# Modular_RFPA_RevA.net
KiCad netlist of a schematic drawn in EAGLE
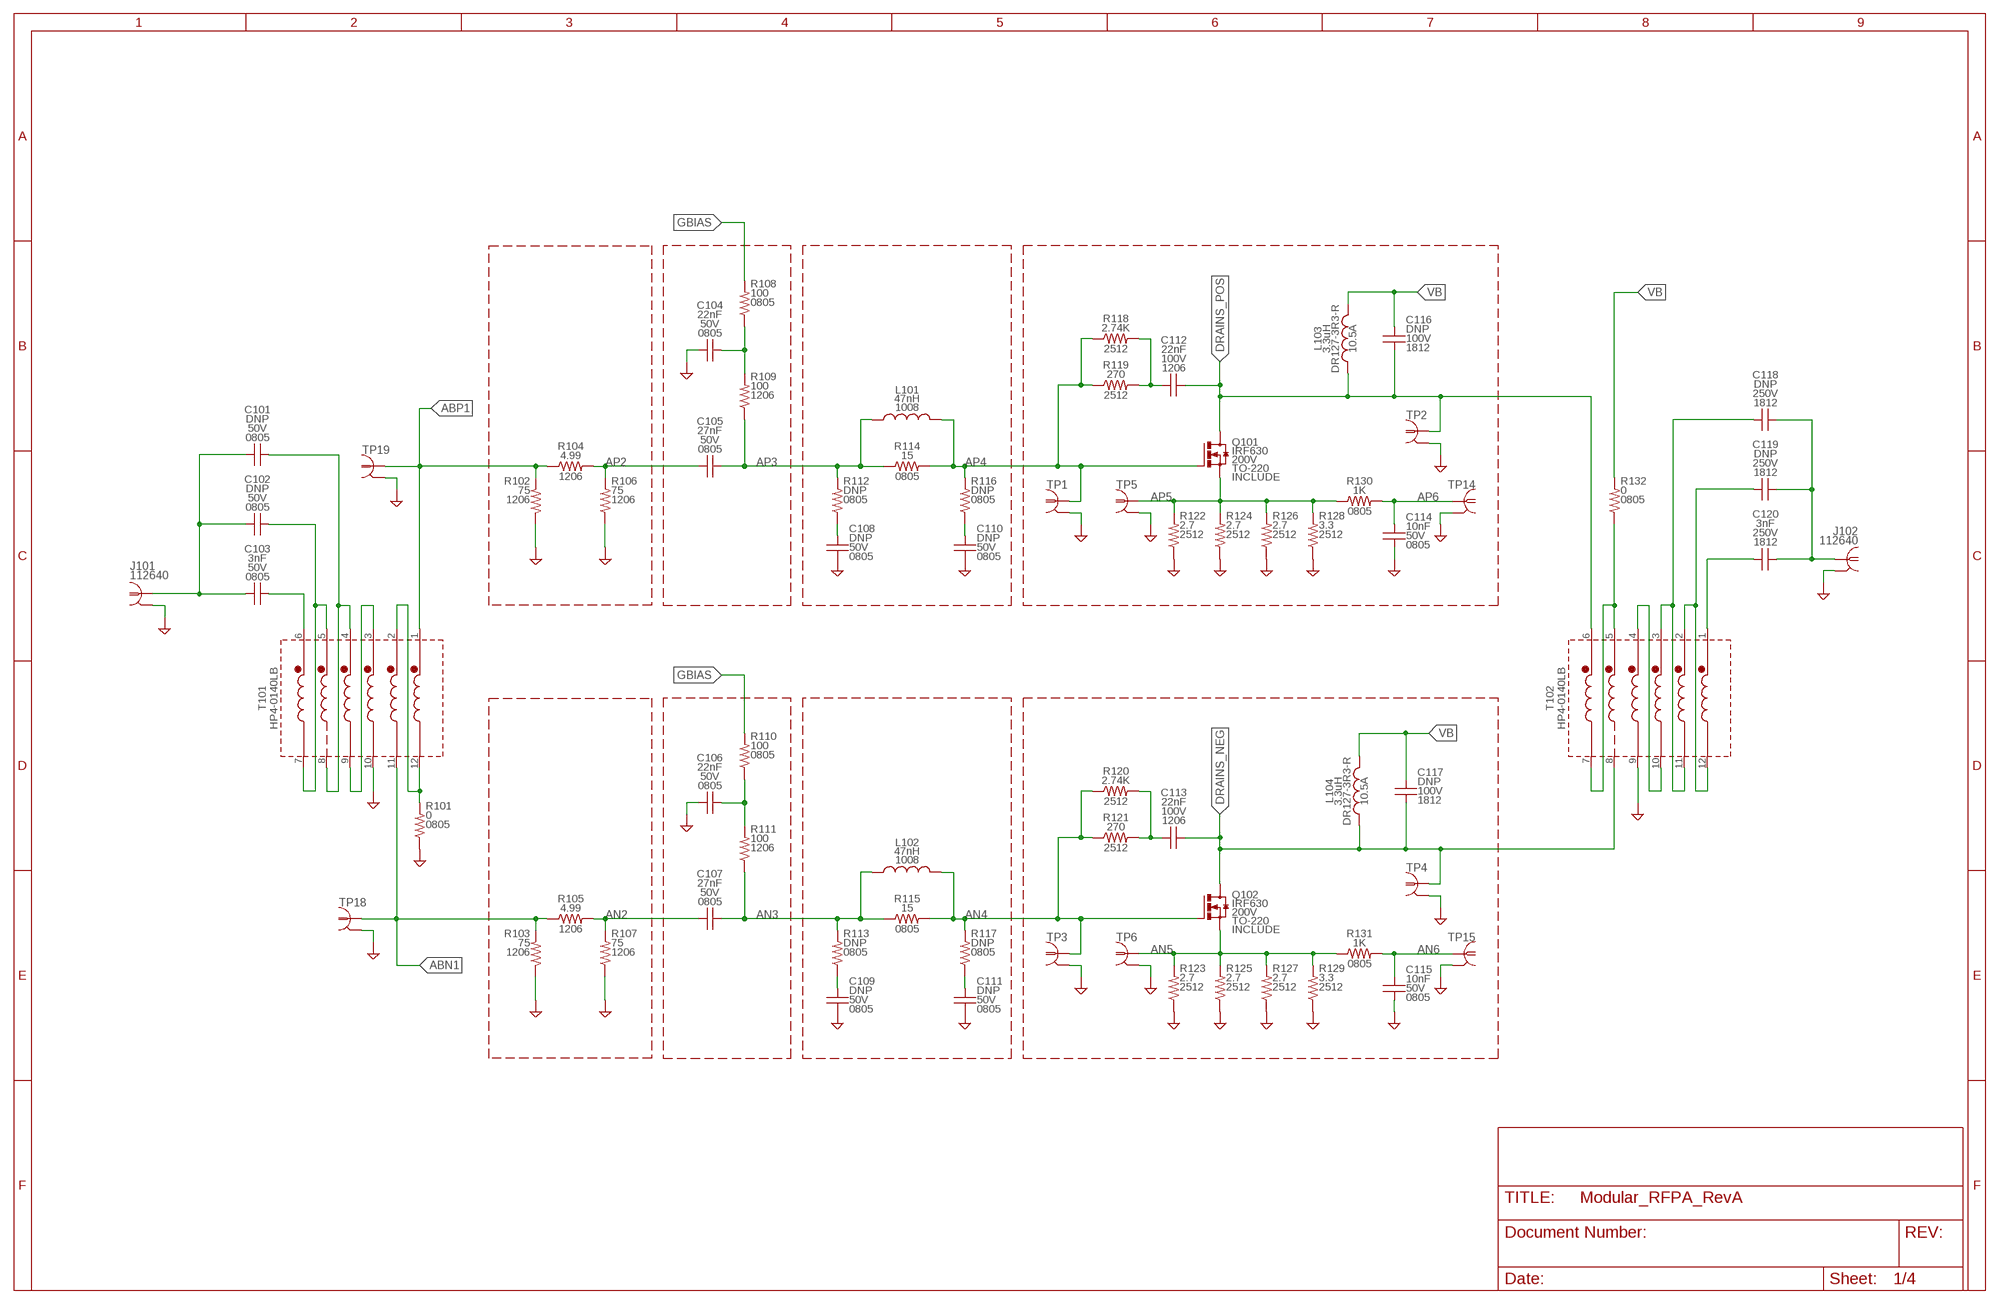
[diagram p0: schematic, sheet 1]
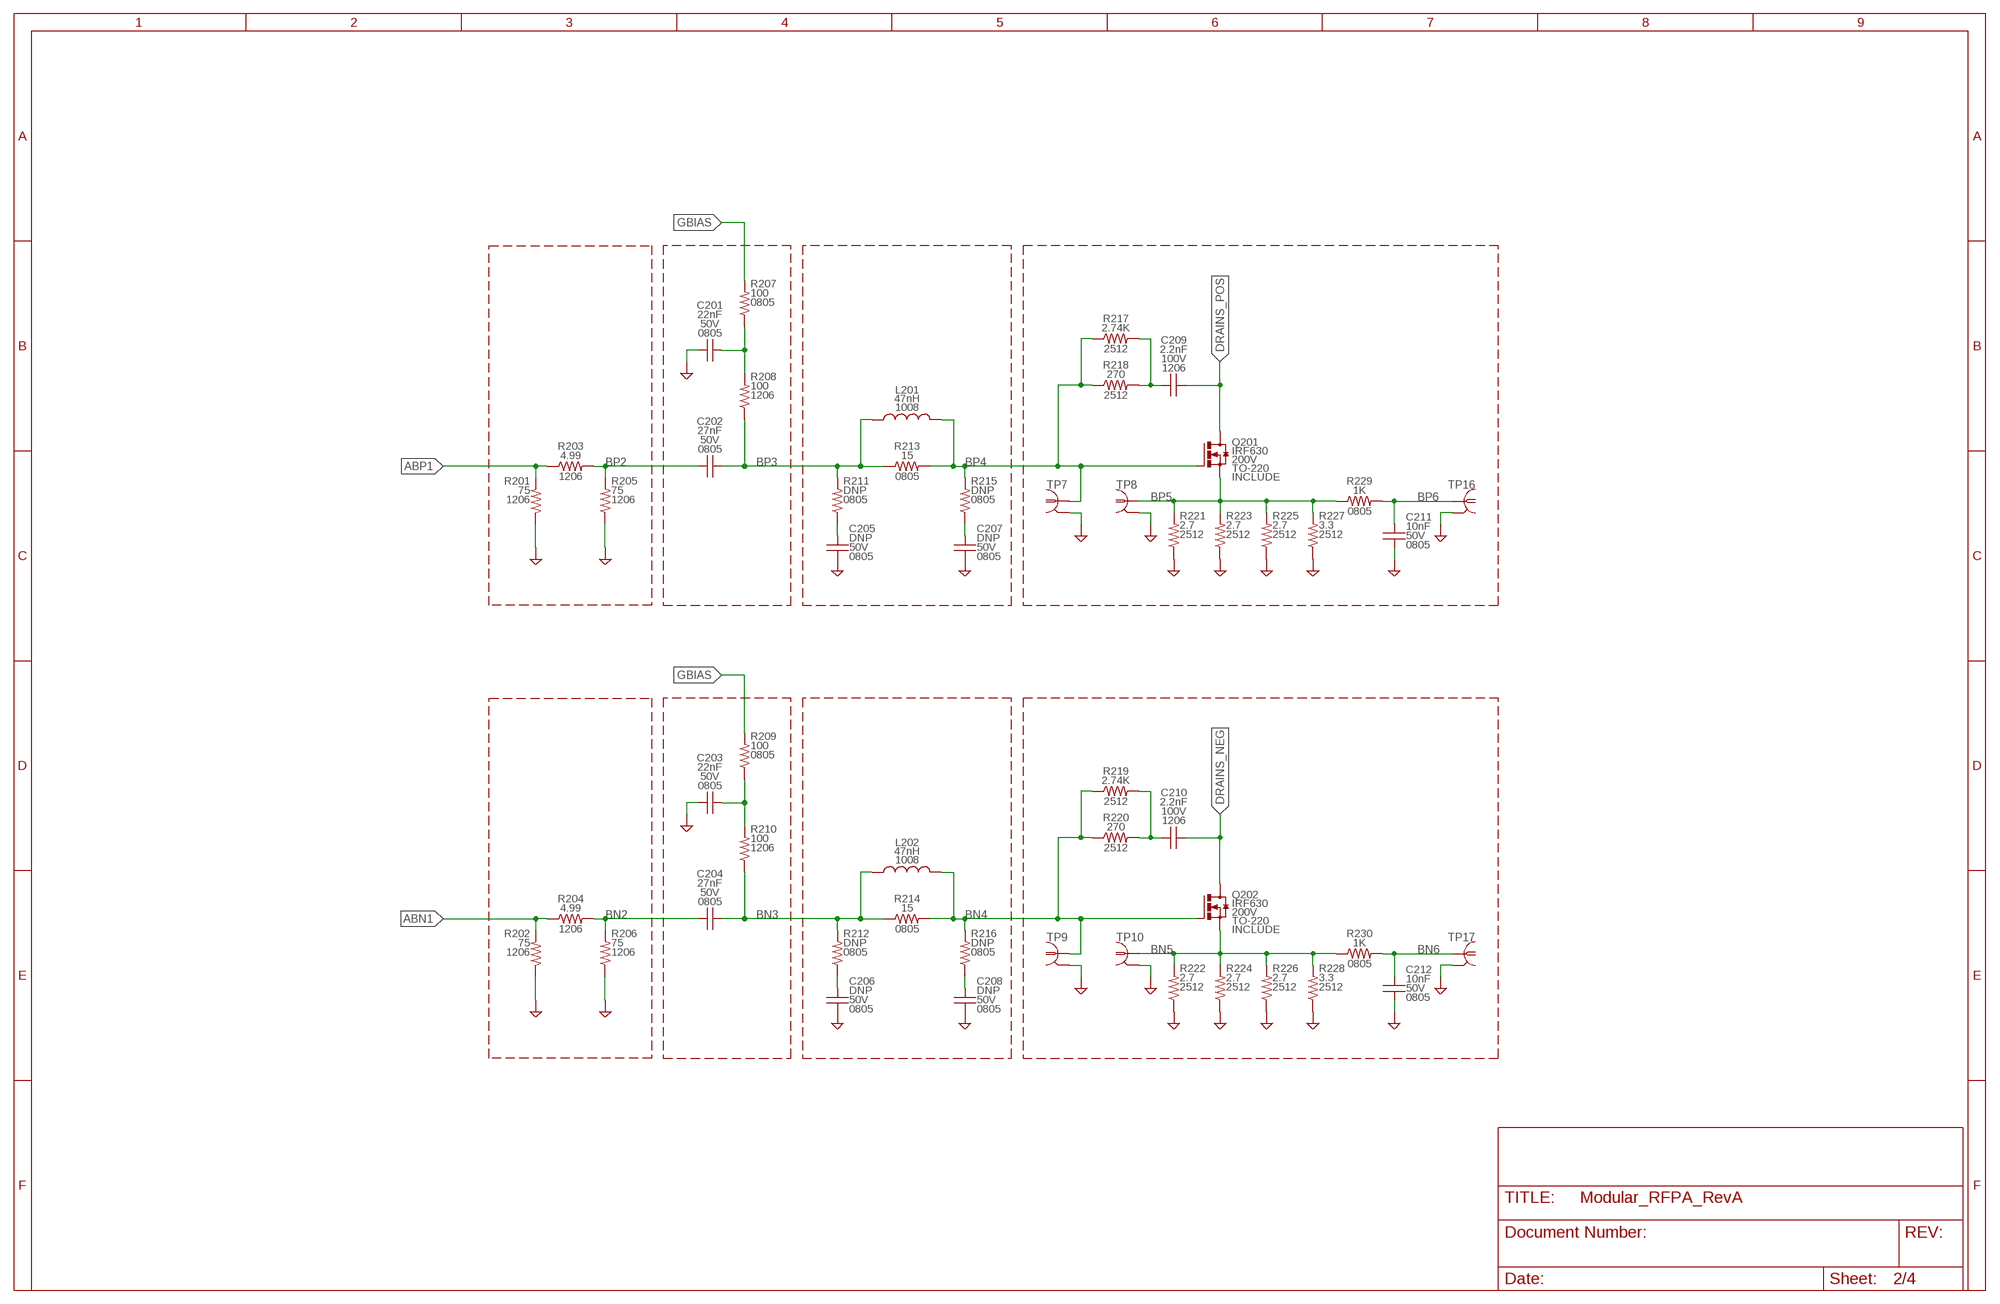
[diagram p1: schematic, sheet 2]
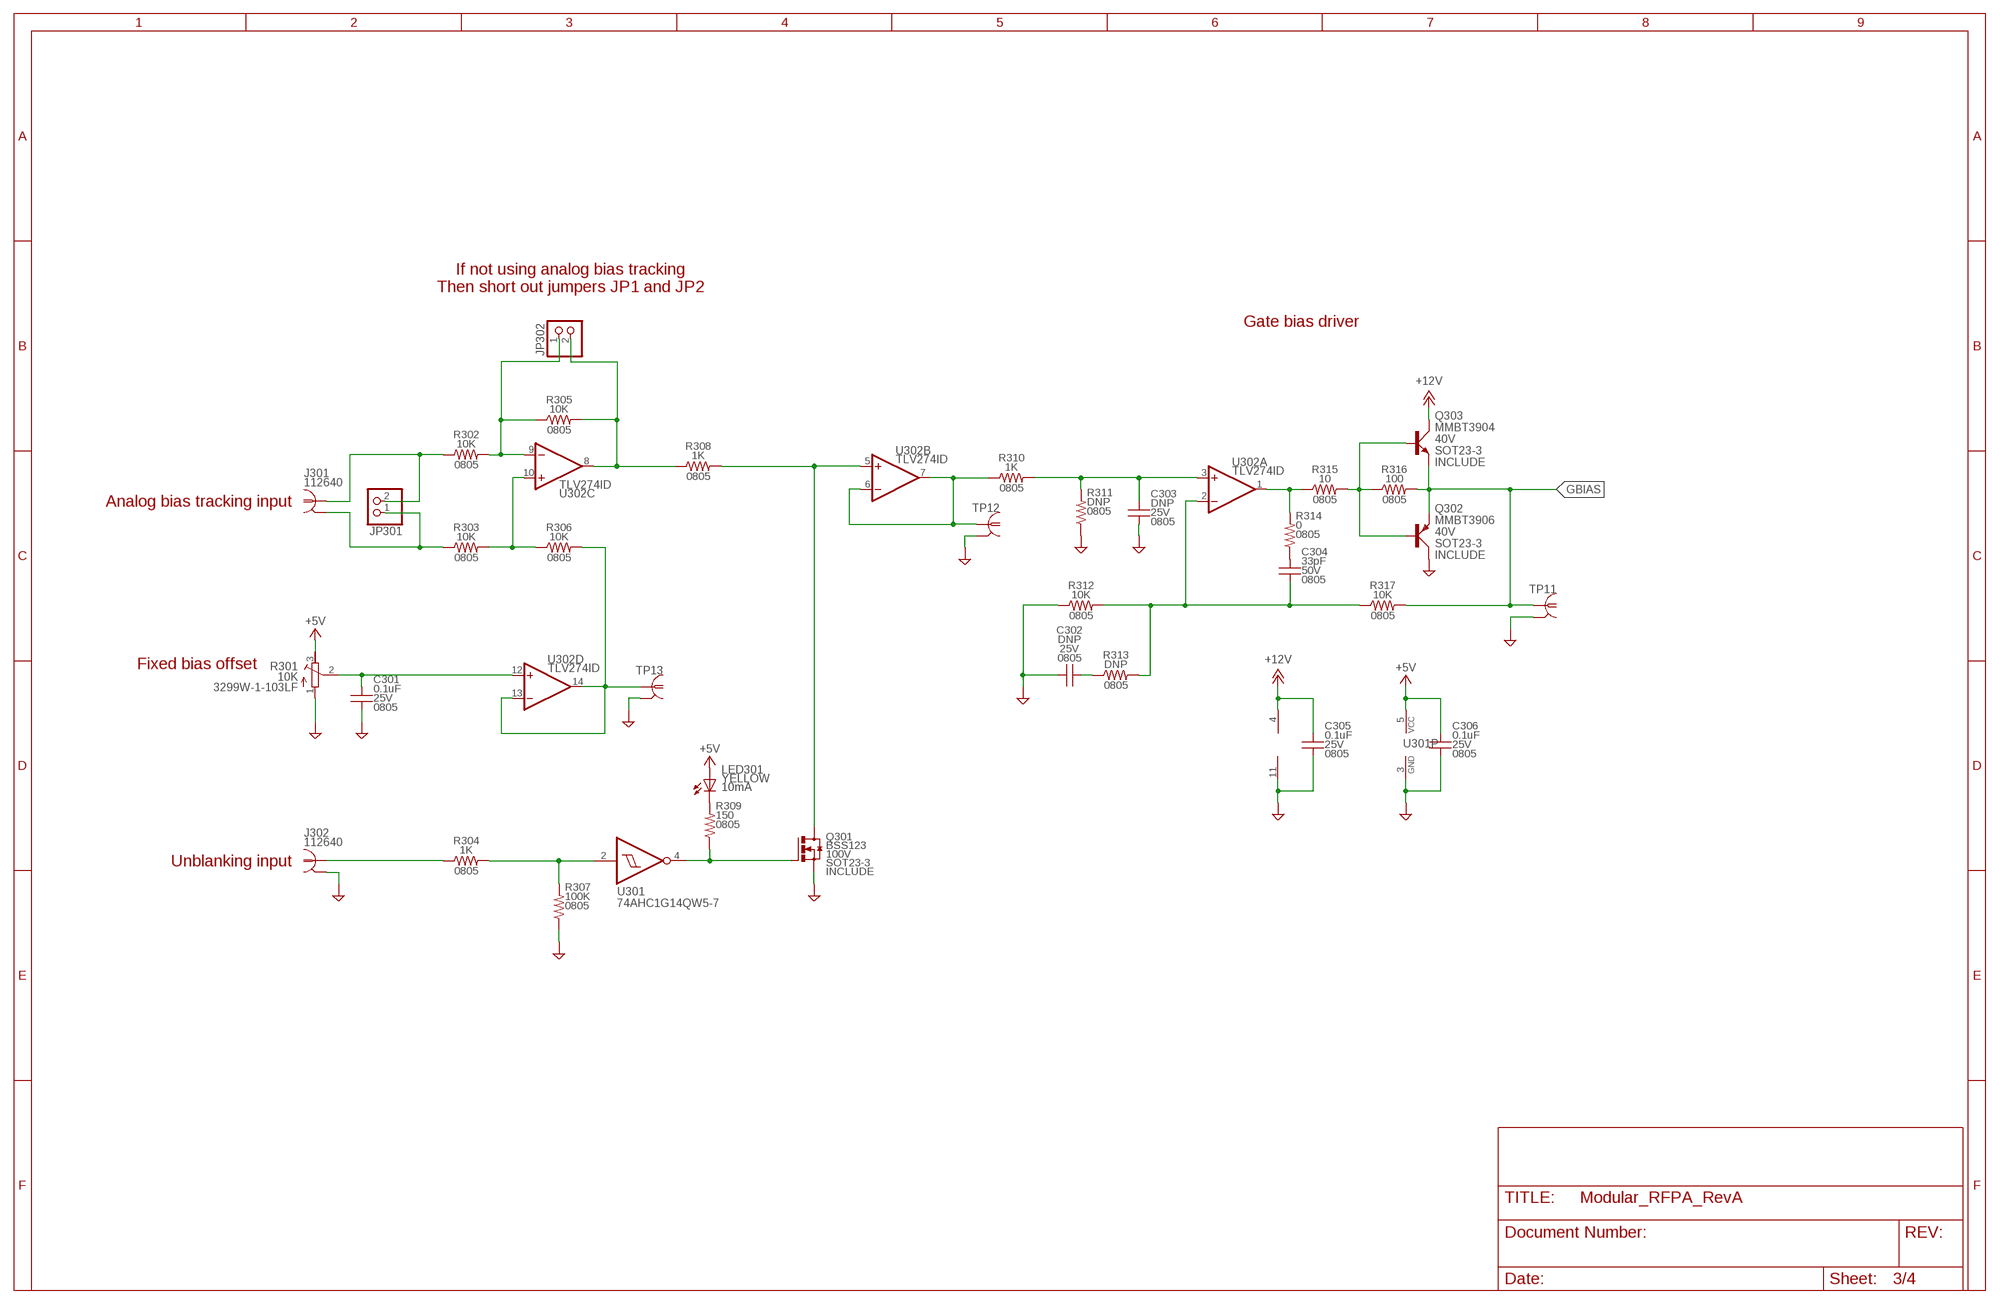
[diagram p2: schematic, sheet 3]
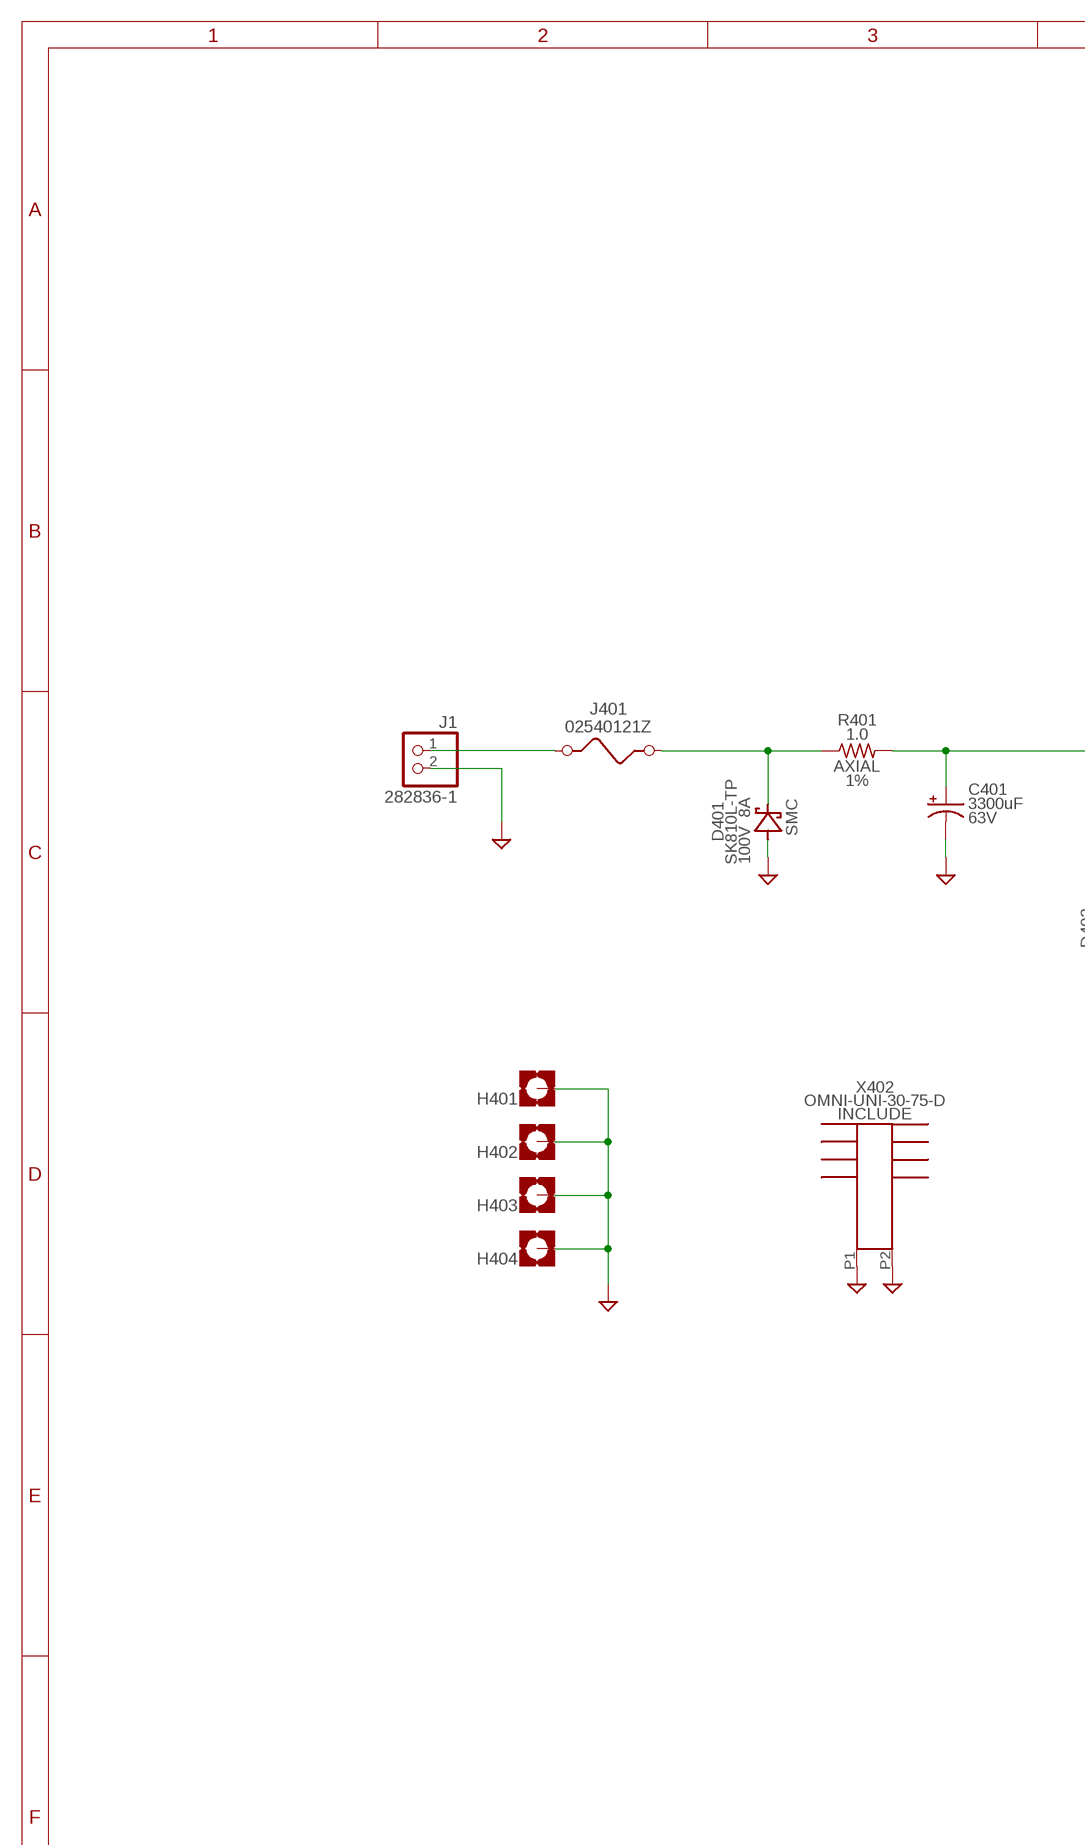
[diagram p3: schematic, sheet 4, part 1 of 2]
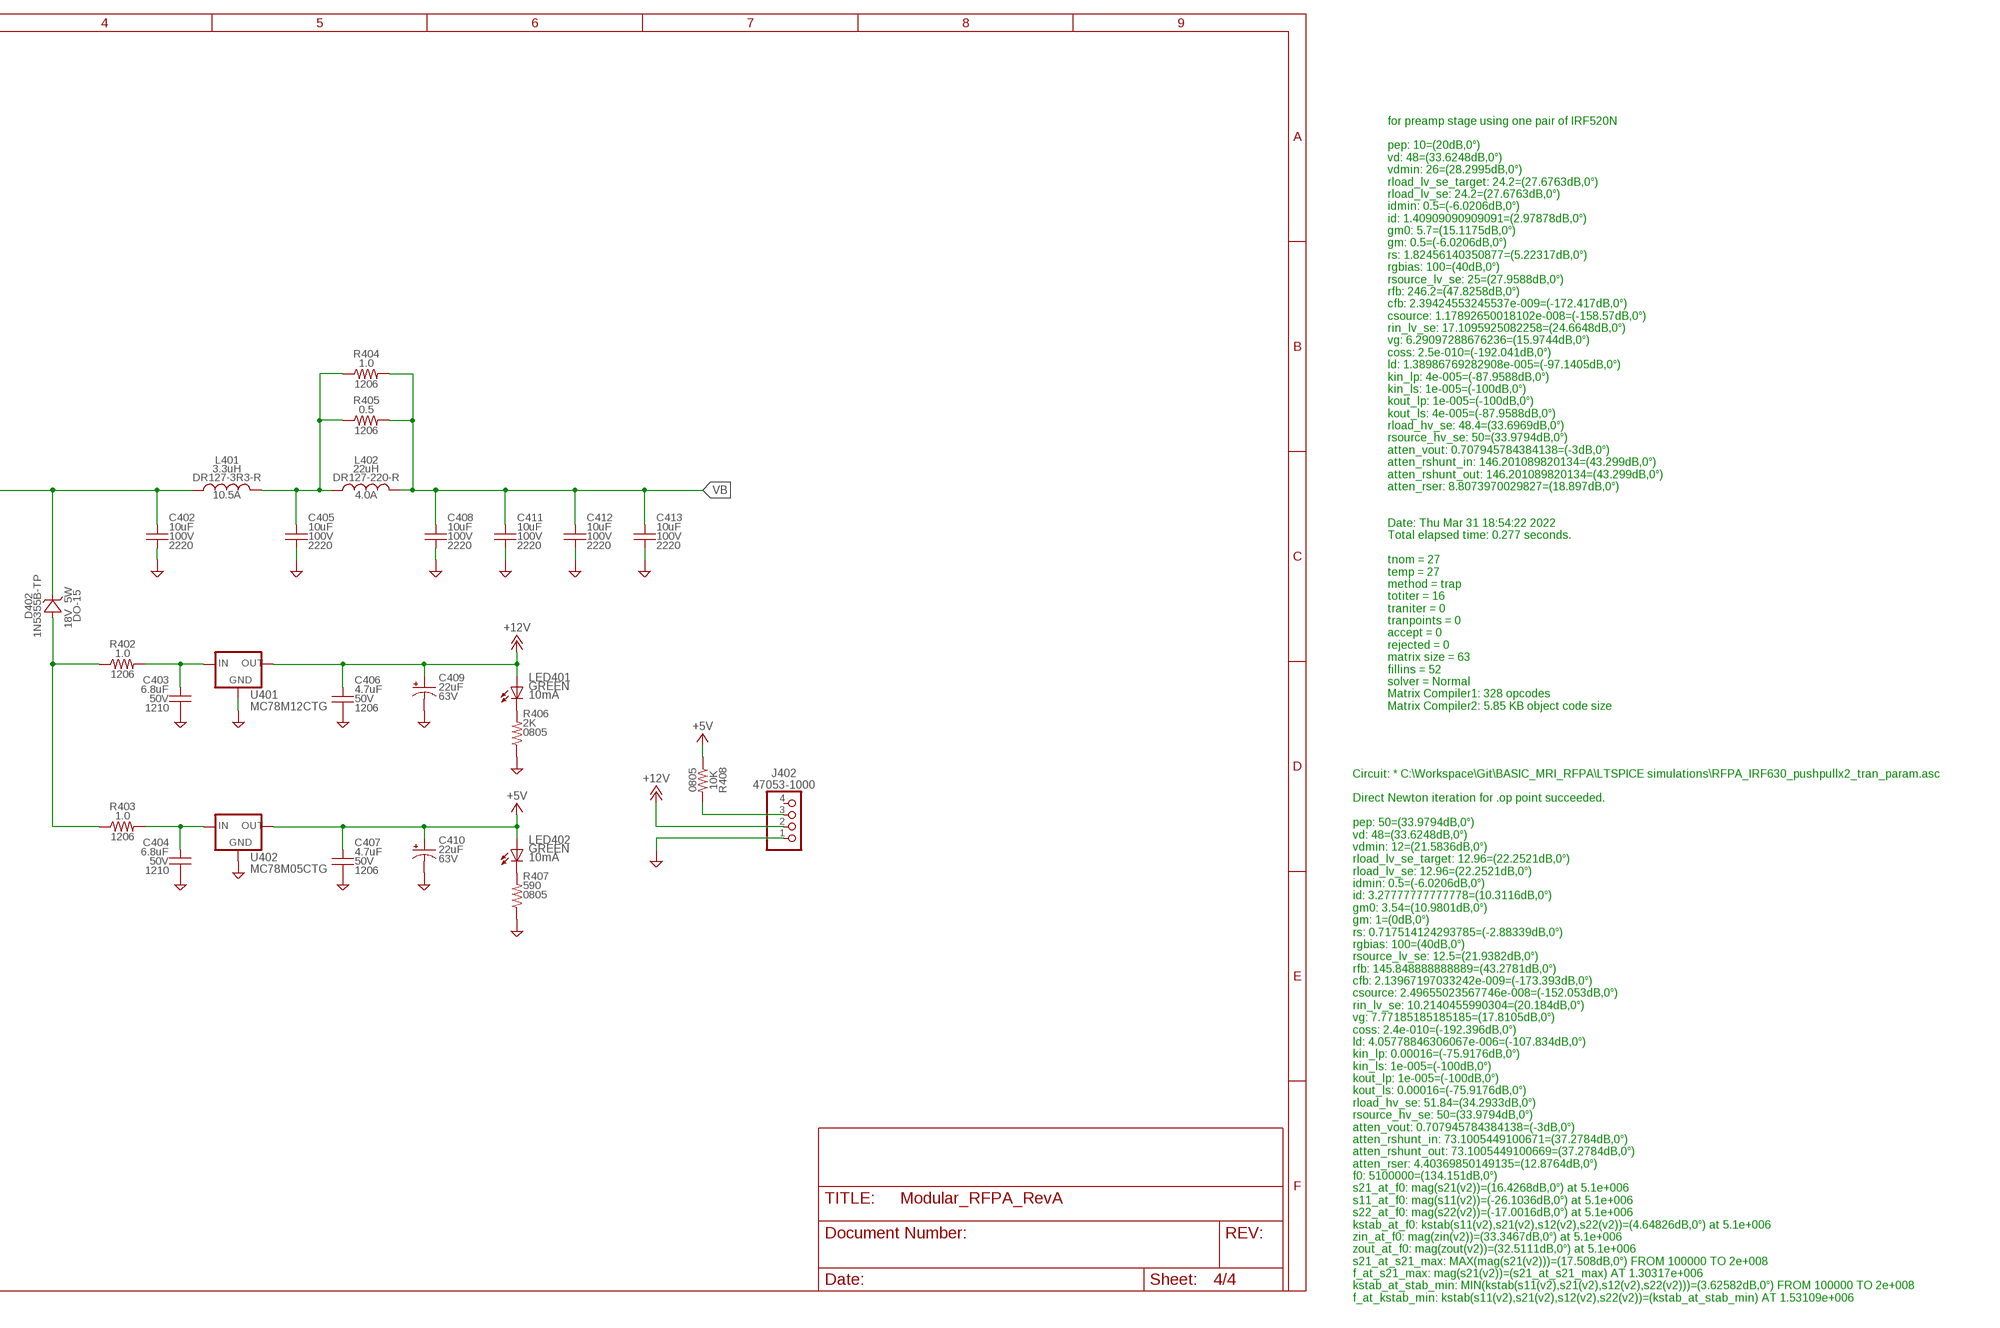
[diagram p4: schematic, sheet 4, part 2 of 2]

(export (version "E")
  (design (tool "Eeschema 10.0.6"))
  (components
    (comp (ref "C301")
      (value "0.1uF")
      (footprint "eagle-import:0805_IPC-7351B")
      (fields (field (name "VOLTAGE") "25V"))
      (libsource (lib "eagle-import") (part "C0805_IPCGEN"))
    )
    (comp (ref "C302")
      (value "DNP")
      (footprint "eagle-import:0805_IPC-7351B")
      (fields (field (name "PACKAGE") "0805") (field (name "BOM") "EXCLUDE") (field (name "VOLTAGE") "25V"))
      (libsource (lib "eagle-import") (part "C0805_IPCGEN"))
    )
    (comp (ref "C303")
      (value "DNP")
      (footprint "eagle-import:0805_IPC-7351B")
      (fields (field (name "BOM") "EXCLUDE") (field (name "VOLTAGE") "25V"))
      (libsource (lib "eagle-import") (part "C0805_IPCGEN"))
    )
    (comp (ref "C304")
      (value "33pF")
      (footprint "eagle-import:0805_IPC-7351B")
      (fields (field (name "VOLTAGE") "50V"))
      (libsource (lib "eagle-import") (part "C0805_IPCGEN"))
    )
    (comp (ref "C305")
      (value "0.1uF")
      (footprint "eagle-import:0805_IPC-7351B")
      (fields (field (name "VOLTAGE") "25V"))
      (libsource (lib "eagle-import") (part "C0805_IPCGEN"))
    )
    (comp (ref "C306")
      (value "0.1uF")
      (footprint "eagle-import:0805_IPC-7351B")
      (fields (field (name "VOLTAGE") "25V"))
      (libsource (lib "eagle-import") (part "C0805_IPCGEN"))
    )
    (comp (ref "J301")
      (value "COAX112640BNC_EDGE")
      (footprint "eagle-import:BNC_EDGE")
      (fields (field (name "PARTNO") "112640"))
      (libsource (lib "eagle-import") (part "COAXBNC_EDGE112640"))
    )
    (comp (ref "J302")
      (value "COAX112640BNC_EDGE")
      (footprint "eagle-import:BNC_EDGE")
      (fields (field (name "PARTNO") "112640"))
      (libsource (lib "eagle-import") (part "COAXBNC_EDGE112640"))
    )
    (comp (ref "JP301")
      (value "PINHD-1X2")
      (footprint "eagle-import:1X02")
      (libsource (lib "eagle-import") (part "PINHD-1X2"))
    )
    (comp (ref "JP302")
      (value "PINHD-1X2")
      (footprint "eagle-import:1X02")
      (libsource (lib "eagle-import") (part "PINHD-1X2"))
    )
    (comp (ref "LED301")
      (value "LEDHLMP-3401-E0002T1_3/4")
      (footprint "eagle-import:LED5MM")
      (fields (field (name "PARTNO") " HLMP-3401-E0002"))
      (libsource (lib "eagle-import") (part "LEDT1_3/4HLMP-3401-E0002"))
    )
    (comp (ref "Q301")
      (value "MOSFET_NBSS123SOT23")
      (footprint "eagle-import:SOT23R_INFINEON")
      (fields (field (name "PARTNO") "BSS123-7-F") (field (name "VOLTAGE") "100V"))
      (libsource (lib "eagle-import") (part "MOSFET_NSOT23BSS123"))
    )
    (comp (ref "Q302")
      (value "PNPSOT23_BEC")
      (footprint "eagle-import:SOT23R_INFINEON")
      (fields (field (name "VOLTAGE") "40V") (field (name "PARTNO") "PMBT3906,215"))
      (libsource (lib "eagle-import") (part "PNPSOT23_BEC"))
    )
    (comp (ref "Q303")
      (value "NPNMMBT3904SOT23_BEC")
      (footprint "eagle-import:SOT23R_INFINEON")
      (fields (field (name "PARTNO") "MMBT3904,215") (field (name "VOLTAGE") "40V"))
      (libsource (lib "eagle-import") (part "NPNSOT23_BECMMBT3904"))
    )
    (comp (ref "R301")
      (value "10K")
      (footprint "eagle-import:RTRIM3299W")
      (fields (field (name "PARTNO") "3299W-1-103LF") (field (name "POWER") "0.5W"))
      (libsource (lib "eagle-import") (part "RTRIM3299WRTRIM-10K-10%-3299W-0.5W"))
    )
    (comp (ref "R302")
      (value "10K")
      (footprint "eagle-import:0805_IPC-7351B")
      (libsource (lib "eagle-import") (part "R900805_IPCGEN"))
    )
    (comp (ref "R303")
      (value "10K")
      (footprint "eagle-import:0805_IPC-7351B")
      (libsource (lib "eagle-import") (part "R900805_IPCGEN"))
    )
    (comp (ref "R304")
      (value "1K")
      (footprint "eagle-import:0805_IPC-7351B")
      (libsource (lib "eagle-import") (part "R900805_IPCGEN"))
    )
    (comp (ref "R305")
      (value "10K")
      (footprint "eagle-import:0805_IPC-7351B")
      (libsource (lib "eagle-import") (part "R900805_IPCGEN"))
    )
    (comp (ref "R306")
      (value "10K")
      (footprint "eagle-import:0805_IPC-7351B")
      (libsource (lib "eagle-import") (part "R900805_IPCGEN"))
    )
    (comp (ref "R307")
      (value "100K")
      (footprint "eagle-import:0805_IPC-7351B")
      (libsource (lib "eagle-import") (part "R0805_IPCGEN"))
    )
    (comp (ref "R308")
      (value "1K")
      (footprint "eagle-import:0805_IPC-7351B")
      (libsource (lib "eagle-import") (part "R900805_IPCGEN"))
    )
    (comp (ref "R309")
      (value "150")
      (footprint "eagle-import:0805_IPC-7351B")
      (libsource (lib "eagle-import") (part "R0805_IPCGEN"))
    )
    (comp (ref "R310")
      (value "1K")
      (footprint "eagle-import:0805_IPC-7351B")
      (libsource (lib "eagle-import") (part "R900805_IPCGEN"))
    )
    (comp (ref "R311")
      (value "DNP")
      (footprint "eagle-import:0805_IPC-7351B")
      (fields (field (name "BOM") "EXCLUDE"))
      (libsource (lib "eagle-import") (part "R0805_IPCGEN"))
    )
    (comp (ref "R312")
      (value "10K")
      (footprint "eagle-import:0805_IPC-7351B")
      (libsource (lib "eagle-import") (part "R900805_IPCGEN"))
    )
    (comp (ref "R313")
      (value "DNP")
      (footprint "eagle-import:0805_IPC-7351B")
      (fields (field (name "BOM") "EXCLUDE"))
      (libsource (lib "eagle-import") (part "R900805_IPCGEN"))
    )
    (comp (ref "R314")
      (value "0")
      (footprint "eagle-import:0805_IPC-7351B")
      (libsource (lib "eagle-import") (part "R0805_IPCGEN"))
    )
    (comp (ref "R315")
      (value "10")
      (footprint "eagle-import:0805_IPC-7351B")
      (libsource (lib "eagle-import") (part "R900805_IPCGEN"))
    )
    (comp (ref "R316")
      (value "100")
      (footprint "eagle-import:0805_IPC-7351B")
      (libsource (lib "eagle-import") (part "R900805_IPCGEN"))
    )
    (comp (ref "R317")
      (value "10K")
      (footprint "eagle-import:0805_IPC-7351B")
      (libsource (lib "eagle-import") (part "R900805_IPCGEN"))
    )
    (comp (ref "TP11")
      (value "PROBE_TPTP_5MM")
      (footprint "eagle-import:PROBE_TP_5MM")
      (libsource (lib "eagle-import") (part "PROBE_TPTP_5MM"))
    )
    (comp (ref "TP12")
      (value "PROBE_TPTP_5MM")
      (footprint "eagle-import:PROBE_TP_5MM")
      (libsource (lib "eagle-import") (part "PROBE_TPTP_5MM"))
    )
    (comp (ref "TP13")
      (value "PROBE_TPTP_5MM")
      (footprint "eagle-import:PROBE_TP_5MM")
      (libsource (lib "eagle-import") (part "PROBE_TPTP_5MM"))
    )
    (comp (ref "U301")
      (value "74AHC1G14DBV")
      (footprint "eagle-import:SOT23-5")
      (description "IC INVERT SCHMITT 1CH 1-IN SOT25")
      (fields
        (field (name "PARTNO") "74AHC1G14QW5-7")
        (field (name "BOM") "INCLUDE")
        (field (name "PACKAGE") "SOT23-5")
        (field (name "VENDOR") "Diodes Inc")
      )
      (libsource (lib "eagle-import") (part "741G14DBVAHC"))
    )
    (comp (ref "U302")
      (value "OPAMP_QUADTLV274IDSOIC14")
      (footprint "eagle-import:SO14")
      (fields (field (name "PARTNO") "TLV274ID"))
      (libsource (lib "eagle-import") (part "OPAMP_QUADSOIC14TLV274ID"))
    )
    (comp (ref "C401")
      (value "3300uF")
      (footprint "eagle-import:EB25D")
      (fields (field (name "PARTNO") "MAL225638332E3") (field (name "VOLTAGE") "63V"))
      (libsource (lib "eagle-import") (part "CPOLEB25DC-3300U-63V-20%-25DX37L-ELEC"))
    )
    (comp (ref "C402")
      (value "10uF")
      (footprint "eagle-import:C2220_CKG57N")
      (fields
        (field (name "BOM") "INCLUDE")
        (field (name "PACKAGE") "2220")
        (field (name "PARTNO") "CGA9N3X7S2A106M230KE")
        (field (name "VOLTAGE") "100V")
      )
      (libsource (lib "eagle-import") (part "CC2220_CKG57NCC-10U-100V-20%-2220-X7T"))
    )
    (comp (ref "C403")
      (value "6.8uF")
      (footprint "eagle-import:C1210")
      (fields (field (name "DIALECTRIC") "X7S") (field (name "VOLTAGE") "50V"))
      (libsource (lib "eagle-import") (part "CC1210GEN"))
    )
    (comp (ref "C404")
      (value "6.8uF")
      (footprint "eagle-import:C1210")
      (fields (field (name "DIALECTRIC") "X7S") (field (name "VOLTAGE") "50V"))
      (libsource (lib "eagle-import") (part "CC1210GEN"))
    )
    (comp (ref "C405")
      (value "10uF")
      (footprint "eagle-import:C2220_CKG57N")
      (fields
        (field (name "BOM") "INCLUDE")
        (field (name "PACKAGE") "2220")
        (field (name "PARTNO") "CGA9N3X7S2A106M230KE")
        (field (name "VOLTAGE") "100V")
      )
      (libsource (lib "eagle-import") (part "CC2220_CKG57NCC-10U-100V-20%-2220-X7T"))
    )
    (comp (ref "C406")
      (value "4.7uF")
      (footprint "eagle-import:C1206")
      (fields (field (name "DIALECTRIC") "X7R") (field (name "VOLTAGE") "50V"))
      (libsource (lib "eagle-import") (part "CC1206GEN"))
    )
    (comp (ref "C407")
      (value "4.7uF")
      (footprint "eagle-import:C1206")
      (fields (field (name "DIALECTRIC") "X7R") (field (name "VOLTAGE") "50V"))
      (libsource (lib "eagle-import") (part "CC1206GEN"))
    )
    (comp (ref "C408")
      (value "10uF")
      (footprint "eagle-import:C2220_CKG57N")
      (fields (field (name "PARTNO") "CGA9N3X7S2A106M230KE") (field (name "VOLTAGE") "100V"))
      (libsource (lib "eagle-import") (part "CC2220_CKG57NCC-10U-100V-20%-2220-X7T"))
    )
    (comp (ref "C409")
      (value "22uF")
      (footprint "eagle-import:E2,5-7")
      (fields (field (name "PARTNO") "860010773010") (field (name "VOLTAGE") "63V"))
      (libsource (lib "eagle-import") (part "CPOLE2,5-7C-22U-63V-20%-6.3DX12.5L-ELEC"))
    )
    (comp (ref "C410")
      (value "22uF")
      (footprint "eagle-import:E2,5-7")
      (fields (field (name "PARTNO") "860010773010") (field (name "VOLTAGE") "63V"))
      (libsource (lib "eagle-import") (part "CPOLE2,5-7C-22U-63V-20%-6.3DX12.5L-ELEC"))
    )
    (comp (ref "C411")
      (value "10uF")
      (footprint "eagle-import:C2220_CKG57N")
      (fields (field (name "PARTNO") "CGA9N3X7S2A106M230KE") (field (name "VOLTAGE") "100V"))
      (libsource (lib "eagle-import") (part "CC2220_CKG57NCC-10U-100V-20%-2220-X7T"))
    )
    (comp (ref "C412")
      (value "10uF")
      (footprint "eagle-import:C2220_CKG57N")
      (fields (field (name "PARTNO") "CGA9N3X7S2A106M230KE") (field (name "VOLTAGE") "100V"))
      (libsource (lib "eagle-import") (part "CC2220_CKG57NCC-10U-100V-20%-2220-X7T"))
    )
    (comp (ref "C413")
      (value "10uF")
      (footprint "eagle-import:C2220_CKG57N")
      (fields (field (name "PARTNO") "CGA9N3X7S2A106M230KE") (field (name "VOLTAGE") "100V"))
      (libsource (lib "eagle-import") (part "CC2220_CKG57NCC-10U-100V-20%-2220-X7T"))
    )
    (comp (ref "D401")
      (value "D-SCHOTTKYSK810L-TPSMC")
      (footprint "eagle-import:DO-214AB(SMC)")
      (fields (field (name "PARTNO") "SK810L-TP") (field (name "VOLTAGE") "100V"))
      (libsource (lib "eagle-import") (part "D-SCHOTTKYSMCSK810L-TP"))
    )
    (comp (ref "D402")
      (value "D-ZENER1N5355B-TPDO15-12")
      (footprint "eagle-import:DO15-12")
      (fields (field (name "PARTNO") "1N5355B-TP") (field (name "POWER") "5W") (field (name "VOLTAGE") "18V"))
      (libsource (lib "eagle-import") (part "D-ZENERDO15-121N5355B-TP"))
    )
    (comp (ref "H401")
      (value "MOUNT-PAD-SQUARE3.2")
      (footprint "eagle-import:3,2-PAD-SQUARE")
      (libsource (lib "eagle-import") (part "MOUNT-PAD-SQUARE3.2"))
    )
    (comp (ref "H402")
      (value "MOUNT-PAD-SQUARE3.2")
      (footprint "eagle-import:3,2-PAD-SQUARE")
      (libsource (lib "eagle-import") (part "MOUNT-PAD-SQUARE3.2"))
    )
    (comp (ref "H403")
      (value "MOUNT-PAD-SQUARE3.2")
      (footprint "eagle-import:3,2-PAD-SQUARE")
      (libsource (lib "eagle-import") (part "MOUNT-PAD-SQUARE3.2"))
    )
    (comp (ref "H404")
      (value "MOUNT-PAD-SQUARE3.2")
      (footprint "eagle-import:3,2-PAD-SQUARE")
      (libsource (lib "eagle-import") (part "MOUNT-PAD-SQUARE3.2"))
    )
    (comp (ref "J1")
      (value "HDR_2X1282836-1282836-1")
      (footprint "eagle-import:W237-02")
      (fields (field (name "PARTNO") "282836-1"))
      (libsource (lib "eagle-import") (part "HDR_2X1282836-1282836-1"))
    )
    (comp (ref "J401")
      (value "FUSE_2P")
      (footprint "eagle-import:02540121Z")
      (fields (field (name "PARTNO") "02540121Z"))
      (libsource (lib "eagle-import") (part "FUSE_2P"))
    )
    (comp (ref "J402")
      (value "KK_PCFAN")
      (footprint "eagle-import:47053-1000")
      (fields (field (name "PARTNO") "47053-1000"))
      (libsource (lib "eagle-import") (part "KK_PCFAN"))
    )
    (comp (ref "L401")
      (value "3.3uH")
      (footprint "eagle-import:DR127")
      (fields (field (name "PARTNO") "DR127-3R3-R"))
      (libsource (lib "eagle-import") (part "LL-3.3U-FERRITE-20%-12.5X12.5MM-10.5A"))
    )
    (comp (ref "L402")
      (value "22uH")
      (footprint "eagle-import:DR127")
      (fields (field (name "PARTNO") "DR127-220-R"))
      (libsource (lib "eagle-import") (part "LL-22U-FERRITE-20%-12.5X12.5MM-4A"))
    )
    (comp (ref "LED401")
      (value "LEDHLMP-3962-F0002T1_3/4")
      (footprint "eagle-import:LED5MM")
      (fields (field (name "PARTNO") "HLMP-3962-F0002"))
      (libsource (lib "eagle-import") (part "LEDT1_3/4HLMP-3962-F0002"))
    )
    (comp (ref "LED402")
      (value "LEDHLMP-3962-F0002T1_3/4")
      (footprint "eagle-import:LED5MM")
      (fields (field (name "PARTNO") "HLMP-3962-F0002"))
      (libsource (lib "eagle-import") (part "LEDT1_3/4HLMP-3962-F0002"))
    )
    (comp (ref "R401")
      (value "1.0")
      (footprint "eagle-import:P0817V")
      (fields (field (name "PARTNO") "PAC300001008FAC000") (field (name "POWER") "3W"))
      (libsource (lib "eagle-import") (part "R90P0817VR-1.0-1%-AXIAL-3W"))
    )
    (comp (ref "R402")
      (value "1.0")
      (footprint "eagle-import:R1206")
      (libsource (lib "eagle-import") (part "R90R1206GEN"))
    )
    (comp (ref "R403")
      (value "1.0")
      (footprint "eagle-import:R1206")
      (libsource (lib "eagle-import") (part "R90R1206GEN"))
    )
    (comp (ref "R404")
      (value "1.0")
      (footprint "eagle-import:1206_IPC-7351B")
      (libsource (lib "eagle-import") (part "R901206_IPCGEN"))
    )
    (comp (ref "R405")
      (value "0.5")
      (footprint "eagle-import:1206_IPC-7351B")
      (libsource (lib "eagle-import") (part "R901206_IPCGEN"))
    )
    (comp (ref "R406")
      (value "2K")
      (footprint "eagle-import:0805_IPC-7351B")
      (libsource (lib "eagle-import") (part "R0805_IPCGEN"))
    )
    (comp (ref "R407")
      (value "590")
      (footprint "eagle-import:0805_IPC-7351B")
      (libsource (lib "eagle-import") (part "R0805_IPCGEN"))
    )
    (comp (ref "R408")
      (value "10K")
      (footprint "eagle-import:0805_IPC-7351B")
      (libsource (lib "eagle-import") (part "R900805_IPCGEN"))
    )
    (comp (ref "U401")
      (value "LDO_3TERMMC78M12CTGTO220_VERT")
      (footprint "eagle-import:TO220BV")
      (fields (field (name "PARTNO") "MC78M12CTG"))
      (libsource (lib "eagle-import") (part "LDO_3TERMTO220_VERTMC78M12CTG"))
    )
    (comp (ref "U402")
      (value "LDO_3TERMMC78M05CTGTO220_VERT")
      (footprint "eagle-import:TO220BV")
      (fields (field (name "PARTNO") "MC78M05CTG"))
      (libsource (lib "eagle-import") (part "LDO_3TERMTO220_VERTMC78M05CTG"))
    )
    (comp (ref "X402")
      (value "HEATSINK_OMNI_DUALOMNI-UNI-30-75-D30-75-D")
      (footprint "eagle-import:OMNI-UNI-30-75-D")
      (fields (field (name "PARTNO") "OMNI-UNI-30-75-D"))
      (libsource (lib "eagle-import") (part "HEATSINK_OMNI_DUAL30-75-DOMNI-UNI-30-75-D"))
    )
    (comp (ref "C201")
      (value "22nF")
      (footprint "eagle-import:0805_IPC-7351B")
      (fields (field (name "PACKAGE") "0805") (field (name "VOLTAGE") "50V"))
      (libsource (lib "eagle-import") (part "C0805_IPCGEN"))
    )
    (comp (ref "C202")
      (value "27nF")
      (footprint "eagle-import:0805_IPC-7351B")
      (fields (field (name "PACKAGE") "0805") (field (name "VOLTAGE") "50V"))
      (libsource (lib "eagle-import") (part "C0805_IPCGEN"))
    )
    (comp (ref "C203")
      (value "22nF")
      (footprint "eagle-import:0805_IPC-7351B")
      (fields (field (name "PACKAGE") "0805") (field (name "VOLTAGE") "50V"))
      (libsource (lib "eagle-import") (part "C0805_IPCGEN"))
    )
    (comp (ref "C204")
      (value "27nF")
      (footprint "eagle-import:0805_IPC-7351B")
      (fields (field (name "PACKAGE") "0805") (field (name "VOLTAGE") "50V"))
      (libsource (lib "eagle-import") (part "C0805_IPCGEN"))
    )
    (comp (ref "C205")
      (value "DNP")
      (footprint "eagle-import:0805_IPC-7351B")
      (fields (field (name "BOM") "EXCLUDE") (field (name "VOLTAGE") "50V"))
      (libsource (lib "eagle-import") (part "C0805_IPCGEN"))
    )
    (comp (ref "C206")
      (value "DNP")
      (footprint "eagle-import:0805_IPC-7351B")
      (fields (field (name "BOM") "EXCLUDE") (field (name "VOLTAGE") "50V"))
      (libsource (lib "eagle-import") (part "C0805_IPCGEN"))
    )
    (comp (ref "C207")
      (value "DNP")
      (footprint "eagle-import:0805_IPC-7351B")
      (fields (field (name "BOM") "EXCLUDE") (field (name "VOLTAGE") "50V"))
      (libsource (lib "eagle-import") (part "C0805_IPCGEN"))
    )
    (comp (ref "C208")
      (value "DNP")
      (footprint "eagle-import:0805_IPC-7351B")
      (fields (field (name "BOM") "EXCLUDE") (field (name "VOLTAGE") "50V"))
      (libsource (lib "eagle-import") (part "C0805_IPCGEN"))
    )
    (comp (ref "C209")
      (value "2.2nF")
      (footprint "eagle-import:C1206")
      (fields (field (name "PACKAGE") "1206") (field (name "VOLTAGE") "100V"))
      (libsource (lib "eagle-import") (part "CC1206GEN"))
    )
    (comp (ref "C210")
      (value "2.2nF")
      (footprint "eagle-import:C1206")
      (fields (field (name "PACKAGE") "1206") (field (name "VOLTAGE") "100V"))
      (libsource (lib "eagle-import") (part "CC1206GEN"))
    )
    (comp (ref "C211")
      (value "10nF")
      (footprint "eagle-import:0805_IPC-7351B")
      (fields (field (name "VOLTAGE") "50V"))
      (libsource (lib "eagle-import") (part "C0805_IPCGEN"))
    )
    (comp (ref "C212")
      (value "10nF")
      (footprint "eagle-import:0805_IPC-7351B")
      (fields (field (name "VOLTAGE") "50V"))
      (libsource (lib "eagle-import") (part "C0805_IPCGEN"))
    )
    (comp (ref "L201")
      (value "47nH")
      (footprint "eagle-import:L1008")
      (fields (field (name "PARTNO") "1008CS-470XJLC"))
      (libsource (lib "eagle-import") (part "L_CHIP1008L-47N-AIR-5%-1008-1A"))
    )
    (comp (ref "L202")
      (value "47nH")
      (footprint "eagle-import:L1008")
      (fields (field (name "PARTNO") "1008CS-470XJLC"))
      (libsource (lib "eagle-import") (part "L_CHIP1008L-47N-AIR-5%-1008-1A"))
    )
    (comp (ref "Q201")
      (value "IRF630")
      (footprint "eagle-import:TO220BV")
      (fields (field (name "VOLTAGE") "200V"))
      (libsource (lib "eagle-import") (part "MOSFET_NTO-220-VERTIRF630"))
    )
    (comp (ref "Q202")
      (value "IRF630")
      (footprint "eagle-import:TO220BV")
      (fields (field (name "VOLTAGE") "200V"))
      (libsource (lib "eagle-import") (part "MOSFET_NTO-220-VERTIRF630"))
    )
    (comp (ref "R201")
      (value "75")
      (footprint "eagle-import:1206_IPC-7351B")
      (libsource (lib "eagle-import") (part "R1206_IPCGEN"))
    )
    (comp (ref "R202")
      (value "75")
      (footprint "eagle-import:1206_IPC-7351B")
      (libsource (lib "eagle-import") (part "R1206_IPCGEN"))
    )
    (comp (ref "R203")
      (value "4.99")
      (footprint "eagle-import:1206_IPC-7351B")
      (libsource (lib "eagle-import") (part "R901206_IPCGEN"))
    )
    (comp (ref "R204")
      (value "4.99")
      (footprint "eagle-import:1206_IPC-7351B")
      (libsource (lib "eagle-import") (part "R901206_IPCGEN"))
    )
    (comp (ref "R205")
      (value "75")
      (footprint "eagle-import:1206_IPC-7351B")
      (libsource (lib "eagle-import") (part "R1206_IPCGEN"))
    )
    (comp (ref "R206")
      (value "75")
      (footprint "eagle-import:1206_IPC-7351B")
      (libsource (lib "eagle-import") (part "R1206_IPCGEN"))
    )
    (comp (ref "R207")
      (value "100")
      (footprint "eagle-import:0805_IPC-7351B")
      (libsource (lib "eagle-import") (part "R0805_IPCGEN"))
    )
    (comp (ref "R208")
      (value "100")
      (footprint "eagle-import:1206_IPC-7351B")
      (libsource (lib "eagle-import") (part "R1206_IPCGEN"))
    )
    (comp (ref "R209")
      (value "100")
      (footprint "eagle-import:0805_IPC-7351B")
      (libsource (lib "eagle-import") (part "R0805_IPCGEN"))
    )
    (comp (ref "R210")
      (value "100")
      (footprint "eagle-import:1206_IPC-7351B")
      (libsource (lib "eagle-import") (part "R1206_IPCGEN"))
    )
    (comp (ref "R211")
      (value "DNP")
      (footprint "eagle-import:0805_IPC-7351B")
      (fields (field (name "BOM") "EXCLUDE"))
      (libsource (lib "eagle-import") (part "R0805_IPCGEN"))
    )
    (comp (ref "R212")
      (value "DNP")
      (footprint "eagle-import:0805_IPC-7351B")
      (fields (field (name "BOM") "EXCLUDE"))
      (libsource (lib "eagle-import") (part "R0805_IPCGEN"))
    )
    (comp (ref "R213")
      (value "15")
      (footprint "eagle-import:0805_IPC-7351B")
      (libsource (lib "eagle-import") (part "R900805_IPCGEN"))
    )
    (comp (ref "R214")
      (value "15")
      (footprint "eagle-import:0805_IPC-7351B")
      (libsource (lib "eagle-import") (part "R900805_IPCGEN"))
    )
    (comp (ref "R215")
      (value "DNP")
      (footprint "eagle-import:0805_IPC-7351B")
      (fields (field (name "BOM") "EXCLUDE"))
      (libsource (lib "eagle-import") (part "R0805_IPCGEN"))
    )
    (comp (ref "R216")
      (value "DNP")
      (footprint "eagle-import:0805_IPC-7351B")
      (fields (field (name "BOM") "EXCLUDE"))
      (libsource (lib "eagle-import") (part "R0805_IPCGEN"))
    )
    (comp (ref "R217")
      (value "2.74K")
      (footprint "eagle-import:R2512")
      (libsource (lib "eagle-import") (part "R90R2512GEN"))
    )
    (comp (ref "R218")
      (value "270")
      (footprint "eagle-import:R2512")
      (libsource (lib "eagle-import") (part "R90R2512GEN"))
    )
    (comp (ref "R219")
      (value "2.74K")
      (footprint "eagle-import:R2512")
      (libsource (lib "eagle-import") (part "R90R2512GEN"))
    )
    (comp (ref "R220")
      (value "270")
      (footprint "eagle-import:R2512")
      (libsource (lib "eagle-import") (part "R90R2512GEN"))
    )
    (comp (ref "R221")
      (value "2.7")
      (footprint "eagle-import:R2512")
      (libsource (lib "eagle-import") (part "RR2512GEN"))
    )
    (comp (ref "R222")
      (value "2.7")
      (footprint "eagle-import:R2512")
      (libsource (lib "eagle-import") (part "RR2512GEN"))
    )
    (comp (ref "R223")
      (value "2.7")
      (footprint "eagle-import:R2512")
      (libsource (lib "eagle-import") (part "RR2512GEN"))
    )
    (comp (ref "R224")
      (value "2.7")
      (footprint "eagle-import:R2512")
      (libsource (lib "eagle-import") (part "RR2512GEN"))
    )
    (comp (ref "R225")
      (value "2.7")
      (footprint "eagle-import:R2512")
      (libsource (lib "eagle-import") (part "RR2512GEN"))
    )
    (comp (ref "R226")
      (value "2.7")
      (footprint "eagle-import:R2512")
      (libsource (lib "eagle-import") (part "RR2512GEN"))
    )
    (comp (ref "R227")
      (value "3.3")
      (footprint "eagle-import:R2512")
      (libsource (lib "eagle-import") (part "RR2512GEN"))
    )
    (comp (ref "R228")
      (value "3.3")
      (footprint "eagle-import:R2512")
      (libsource (lib "eagle-import") (part "RR2512GEN"))
    )
    (comp (ref "R229")
      (value "1K")
      (footprint "eagle-import:0805_IPC-7351B")
      (libsource (lib "eagle-import") (part "R900805_IPCGEN"))
    )
    (comp (ref "R230")
      (value "1K")
      (footprint "eagle-import:0805_IPC-7351B")
      (libsource (lib "eagle-import") (part "R900805_IPCGEN"))
    )
    (comp (ref "TP7")
      (value "PROBE_TPTP_5MM")
      (footprint "eagle-import:PROBE_TP_5MM")
      (libsource (lib "eagle-import") (part "PROBE_TPTP_5MM"))
    )
    (comp (ref "TP8")
      (value "PROBE_TPTP_7P5MM")
      (footprint "eagle-import:PROBE_TP_7P5MM")
      (libsource (lib "eagle-import") (part "PROBE_TPTP_7P5MM"))
    )
    (comp (ref "TP9")
      (value "PROBE_TPTP_5MM")
      (footprint "eagle-import:PROBE_TP_5MM")
      (libsource (lib "eagle-import") (part "PROBE_TPTP_5MM"))
    )
    (comp (ref "TP10")
      (value "PROBE_TPTP_5MM")
      (footprint "eagle-import:PROBE_TP_5MM")
      (libsource (lib "eagle-import") (part "PROBE_TPTP_5MM"))
    )
    (comp (ref "TP16")
      (value "PROBE_TPTP_5MM")
      (footprint "eagle-import:PROBE_TP_5MM")
      (libsource (lib "eagle-import") (part "PROBE_TPTP_5MM"))
    )
    (comp (ref "TP17")
      (value "PROBE_TPTP_7P5MM")
      (footprint "eagle-import:PROBE_TP_7P5MM")
      (libsource (lib "eagle-import") (part "PROBE_TPTP_7P5MM"))
    )
    (comp (ref "C101")
      (value "DNP")
      (footprint "eagle-import:0805_IPC-7351B")
      (fields (field (name "PACKAGE") "0805") (field (name "BOM") "EXCLUDE") (field (name "VOLTAGE") "50V"))
      (libsource (lib "eagle-import") (part "C0805_IPCGEN"))
    )
    (comp (ref "C102")
      (value "DNP")
      (footprint "eagle-import:0805_IPC-7351B")
      (fields (field (name "PACKAGE") "0805") (field (name "BOM") "EXCLUDE") (field (name "VOLTAGE") "50V"))
      (libsource (lib "eagle-import") (part "C0805_IPCGEN"))
    )
    (comp (ref "C103")
      (value "3nF")
      (footprint "eagle-import:0805_IPC-7351B")
      (fields (field (name "PACKAGE") "0805") (field (name "VOLTAGE") "50V"))
      (libsource (lib "eagle-import") (part "C0805_IPCGEN"))
    )
    (comp (ref "C104")
      (value "22nF")
      (footprint "eagle-import:0805_IPC-7351B")
      (fields (field (name "BOM") "INCLUDE") (field (name "PACKAGE") "0805") (field (name "VOLTAGE") "50V"))
      (libsource (lib "eagle-import") (part "C0805_IPCGEN"))
    )
    (comp (ref "C105")
      (value "27nF")
      (footprint "eagle-import:0805_IPC-7351B")
      (fields (field (name "PACKAGE") "0805") (field (name "VOLTAGE") "50V"))
      (libsource (lib "eagle-import") (part "C0805_IPCGEN"))
    )
    (comp (ref "C106")
      (value "22nF")
      (footprint "eagle-import:0805_IPC-7351B")
      (fields (field (name "PACKAGE") "0805") (field (name "VOLTAGE") "50V"))
      (libsource (lib "eagle-import") (part "C0805_IPCGEN"))
    )
    (comp (ref "C107")
      (value "27nF")
      (footprint "eagle-import:0805_IPC-7351B")
      (fields (field (name "PACKAGE") "0805") (field (name "VOLTAGE") "50V"))
      (libsource (lib "eagle-import") (part "C0805_IPCGEN"))
    )
    (comp (ref "C108")
      (value "DNP")
      (footprint "eagle-import:0805_IPC-7351B")
      (fields (field (name "BOM") "EXCLUDE") (field (name "VOLTAGE") "50V"))
      (libsource (lib "eagle-import") (part "C0805_IPCGEN"))
    )
    (comp (ref "C109")
      (value "DNP")
      (footprint "eagle-import:0805_IPC-7351B")
      (fields (field (name "BOM") "EXCLUDE") (field (name "VOLTAGE") "50V"))
      (libsource (lib "eagle-import") (part "C0805_IPCGEN"))
    )
    (comp (ref "C110")
      (value "DNP")
      (footprint "eagle-import:0805_IPC-7351B")
      (fields (field (name "BOM") "EXCLUDE") (field (name "VOLTAGE") "50V"))
      (libsource (lib "eagle-import") (part "C0805_IPCGEN"))
    )
    (comp (ref "C111")
      (value "DNP")
      (footprint "eagle-import:0805_IPC-7351B")
      (fields (field (name "BOM") "EXCLUDE") (field (name "VOLTAGE") "50V"))
      (libsource (lib "eagle-import") (part "C0805_IPCGEN"))
    )
    (comp (ref "C112")
      (value "22nF")
      (footprint "eagle-import:C1206")
      (fields (field (name "PACKAGE") "1206") (field (name "VOLTAGE") "100V"))
      (libsource (lib "eagle-import") (part "CC1206GEN"))
    )
    (comp (ref "C113")
      (value "22nF")
      (footprint "eagle-import:C1206")
      (fields (field (name "PACKAGE") "1206") (field (name "VOLTAGE") "100V"))
      (libsource (lib "eagle-import") (part "CC1206GEN"))
    )
    (comp (ref "C114")
      (value "10nF")
      (footprint "eagle-import:0805_IPC-7351B")
      (fields (field (name "VOLTAGE") "50V"))
      (libsource (lib "eagle-import") (part "C0805_IPCGEN"))
    )
    (comp (ref "C115")
      (value "10nF")
      (footprint "eagle-import:0805_IPC-7351B")
      (fields (field (name "VOLTAGE") "50V"))
      (libsource (lib "eagle-import") (part "C0805_IPCGEN"))
    )
    (comp (ref "C116")
      (value "DNP")
      (footprint "eagle-import:C1812")
      (fields (field (name "BOM") "EXCLUDE") (field (name "VOLTAGE") "100V"))
      (libsource (lib "eagle-import") (part "CC1812GEN"))
    )
    (comp (ref "C117")
      (value "DNP")
      (footprint "eagle-import:C1812")
      (fields (field (name "BOM") "EXCLUDE") (field (name "VOLTAGE") "100V"))
      (libsource (lib "eagle-import") (part "CC1812GEN"))
    )
    (comp (ref "C118")
      (value "DNP")
      (footprint "eagle-import:C1812")
      (fields (field (name "PACKAGE") "1812") (field (name "BOM") "EXCLUDE") (field (name "VOLTAGE") "250V"))
      (libsource (lib "eagle-import") (part "CC1812GEN"))
    )
    (comp (ref "C119")
      (value "DNP")
      (footprint "eagle-import:C1812")
      (fields (field (name "PACKAGE") "1812") (field (name "BOM") "EXCLUDE") (field (name "VOLTAGE") "250V"))
      (libsource (lib "eagle-import") (part "CC1812GEN"))
    )
    (comp (ref "C120")
      (value "3nF")
      (footprint "eagle-import:C1812")
      (fields (field (name "PACKAGE") "1812") (field (name "VOLTAGE") "250V"))
      (libsource (lib "eagle-import") (part "CC1812GEN"))
    )
    (comp (ref "J101")
      (value "COAX112640BNC_EDGE")
      (footprint "eagle-import:BNC_EDGE")
      (fields (field (name "PARTNO") "112640"))
      (libsource (lib "eagle-import") (part "COAXBNC_EDGE112640"))
    )
    (comp (ref "J102")
      (value "COAX112640BNC_EDGE")
      (footprint "eagle-import:BNC_EDGE")
      (fields (field (name "PARTNO") "112640"))
      (libsource (lib "eagle-import") (part "COAXBNC_EDGE112640"))
    )
    (comp (ref "L101")
      (value "47nH")
      (footprint "eagle-import:L1008")
      (fields (field (name "PARTNO") "1008CS-470XJLC"))
      (libsource (lib "eagle-import") (part "L_CHIP1008L-47N-AIR-5%-1008-1A"))
    )
    (comp (ref "L102")
      (value "47nH")
      (footprint "eagle-import:L1008")
      (fields (field (name "PARTNO") "1008CS-470XJLC"))
      (libsource (lib "eagle-import") (part "L_CHIP1008L-47N-AIR-5%-1008-1A"))
    )
    (comp (ref "L103")
      (value "3.3uH")
      (footprint "eagle-import:DR127")
      (fields (field (name "PARTNO") "DR127-3R3-R"))
      (libsource (lib "eagle-import") (part "LL-3.3U-FERRITE-20%-12.5X12.5MM-10.5A"))
    )
    (comp (ref "L104")
      (value "3.3uH")
      (footprint "eagle-import:DR127")
      (fields (field (name "PARTNO") "DR127-3R3-R"))
      (libsource (lib "eagle-import") (part "LL-3.3U-FERRITE-20%-12.5X12.5MM-10.5A"))
    )
    (comp (ref "Q101")
      (value "IRF520N")
      (footprint "eagle-import:TO220BV")
      (fields (field (name "PARTNO") "IRF630") (field (name "VOLTAGE") "200V"))
      (libsource (lib "eagle-import") (part "MOSFET_NTO-220-VERTIRF630"))
    )
    (comp (ref "Q102")
      (value "IRF630")
      (footprint "eagle-import:TO220BV")
      (fields (field (name "VOLTAGE") "200V"))
      (libsource (lib "eagle-import") (part "MOSFET_NTO-220-VERTIRF630"))
    )
    (comp (ref "R101")
      (value "0")
      (footprint "eagle-import:0805_IPC-7351B")
      (libsource (lib "eagle-import") (part "R0805_IPCGEN"))
    )
    (comp (ref "R102")
      (value "75")
      (footprint "eagle-import:1206_IPC-7351B")
      (libsource (lib "eagle-import") (part "R1206_IPCGEN"))
    )
    (comp (ref "R103")
      (value "75")
      (footprint "eagle-import:1206_IPC-7351B")
      (libsource (lib "eagle-import") (part "R1206_IPCGEN"))
    )
    (comp (ref "R104")
      (value "4.99")
      (footprint "eagle-import:1206_IPC-7351B")
      (libsource (lib "eagle-import") (part "R901206_IPCGEN"))
    )
    (comp (ref "R105")
      (value "4.99")
      (footprint "eagle-import:1206_IPC-7351B")
      (libsource (lib "eagle-import") (part "R901206_IPCGEN"))
    )
    (comp (ref "R106")
      (value "75")
      (footprint "eagle-import:1206_IPC-7351B")
      (libsource (lib "eagle-import") (part "R1206_IPCGEN"))
    )
    (comp (ref "R107")
      (value "75")
      (footprint "eagle-import:1206_IPC-7351B")
      (libsource (lib "eagle-import") (part "R1206_IPCGEN"))
    )
    (comp (ref "R108")
      (value "100")
      (footprint "eagle-import:0805_IPC-7351B")
      (libsource (lib "eagle-import") (part "R0805_IPCGEN"))
    )
    (comp (ref "R109")
      (value "100")
      (footprint "eagle-import:1206_IPC-7351B")
      (libsource (lib "eagle-import") (part "R1206_IPCGEN"))
    )
    (comp (ref "R110")
      (value "100")
      (footprint "eagle-import:0805_IPC-7351B")
      (libsource (lib "eagle-import") (part "R0805_IPCGEN"))
    )
    (comp (ref "R111")
      (value "100")
      (footprint "eagle-import:1206_IPC-7351B")
      (libsource (lib "eagle-import") (part "R1206_IPCGEN"))
    )
    (comp (ref "R112")
      (value "DNP")
      (footprint "eagle-import:0805_IPC-7351B")
      (fields (field (name "BOM") "EXCLUDE"))
      (libsource (lib "eagle-import") (part "R0805_IPCGEN"))
    )
    (comp (ref "R113")
      (value "DNP")
      (footprint "eagle-import:0805_IPC-7351B")
      (fields (field (name "BOM") "EXCLUDE"))
      (libsource (lib "eagle-import") (part "R0805_IPCGEN"))
    )
    (comp (ref "R114")
      (value "15")
      (footprint "eagle-import:0805_IPC-7351B")
      (libsource (lib "eagle-import") (part "R900805_IPCGEN"))
    )
    (comp (ref "R115")
      (value "15")
      (footprint "eagle-import:0805_IPC-7351B")
      (libsource (lib "eagle-import") (part "R900805_IPCGEN"))
    )
    (comp (ref "R116")
      (value "DNP")
      (footprint "eagle-import:0805_IPC-7351B")
      (fields (field (name "BOM") "EXCLUDE"))
      (libsource (lib "eagle-import") (part "R0805_IPCGEN"))
    )
    (comp (ref "R117")
      (value "DNP")
      (footprint "eagle-import:0805_IPC-7351B")
      (fields (field (name "BOM") "EXCLUDE"))
      (libsource (lib "eagle-import") (part "R0805_IPCGEN"))
    )
    (comp (ref "R118")
      (value "2.74K")
      (footprint "eagle-import:R2512")
      (libsource (lib "eagle-import") (part "R90R2512GEN"))
    )
    (comp (ref "R119")
      (value "270")
      (footprint "eagle-import:R2512")
      (libsource (lib "eagle-import") (part "R90R2512GEN"))
    )
    (comp (ref "R120")
      (value "2.74K")
      (footprint "eagle-import:R2512")
      (libsource (lib "eagle-import") (part "R90R2512GEN"))
    )
    (comp (ref "R121")
      (value "270")
      (footprint "eagle-import:R2512")
      (libsource (lib "eagle-import") (part "R90R2512GEN"))
    )
    (comp (ref "R122")
      (value "2.7")
      (footprint "eagle-import:R2512")
      (libsource (lib "eagle-import") (part "RR2512GEN"))
    )
    (comp (ref "R123")
      (value "2.7")
      (footprint "eagle-import:R2512")
      (libsource (lib "eagle-import") (part "RR2512GEN"))
    )
    (comp (ref "R124")
      (value "2.7")
      (footprint "eagle-import:R2512")
      (libsource (lib "eagle-import") (part "RR2512GEN"))
    )
    (comp (ref "R125")
      (value "2.7")
      (footprint "eagle-import:R2512")
      (libsource (lib "eagle-import") (part "RR2512GEN"))
    )
    (comp (ref "R126")
      (value "2.7")
      (footprint "eagle-import:R2512")
      (libsource (lib "eagle-import") (part "RR2512GEN"))
    )
    (comp (ref "R127")
      (value "2.7")
      (footprint "eagle-import:R2512")
      (libsource (lib "eagle-import") (part "RR2512GEN"))
    )
    (comp (ref "R128")
      (value "3.3")
      (footprint "eagle-import:R2512")
      (libsource (lib "eagle-import") (part "RR2512GEN"))
    )
    (comp (ref "R129")
      (value "3.3")
      (footprint "eagle-import:R2512")
      (libsource (lib "eagle-import") (part "RR2512GEN"))
    )
    (comp (ref "R130")
      (value "1K")
      (footprint "eagle-import:0805_IPC-7351B")
      (libsource (lib "eagle-import") (part "R900805_IPCGEN"))
    )
    (comp (ref "R131")
      (value "1K")
      (footprint "eagle-import:0805_IPC-7351B")
      (libsource (lib "eagle-import") (part "R900805_IPCGEN"))
    )
    (comp (ref "R132")
      (value "0")
      (footprint "eagle-import:0805_IPC-7351B")
      (libsource (lib "eagle-import") (part "R0805_IPCGEN"))
    )
    (comp (ref "T101")
      (value "HP4_TRAFO")
      (footprint "eagle-import:HP4")
      (fields (field (name "PARTNO") "HP4-0140LB"))
      (libsource (lib "eagle-import") (part "HP4_TRAFO"))
    )
    (comp (ref "T102")
      (value "HP4_TRAFO")
      (footprint "eagle-import:HP4")
      (fields (field (name "PARTNO") "HP4-0140LB"))
      (libsource (lib "eagle-import") (part "HP4_TRAFO"))
    )
    (comp (ref "TP1")
      (value "PROBE_TPTP_5MM")
      (footprint "eagle-import:PROBE_TP_5MM")
      (libsource (lib "eagle-import") (part "PROBE_TPTP_5MM"))
    )
    (comp (ref "TP2")
      (value "PROBE_TPTP_7P5MM")
      (footprint "eagle-import:PROBE_TP_7P5MM")
      (libsource (lib "eagle-import") (part "PROBE_TPTP_7P5MM"))
    )
    (comp (ref "TP3")
      (value "PROBE_TPTP_5MM")
      (footprint "eagle-import:PROBE_TP_5MM")
      (libsource (lib "eagle-import") (part "PROBE_TPTP_5MM"))
    )
    (comp (ref "TP4")
      (value "PROBE_TPTP_7P5MM")
      (footprint "eagle-import:PROBE_TP_7P5MM")
      (libsource (lib "eagle-import") (part "PROBE_TPTP_7P5MM"))
    )
    (comp (ref "TP5")
      (value "PROBE_TPTP_7P5MM")
      (footprint "eagle-import:PROBE_TP_7P5MM")
      (libsource (lib "eagle-import") (part "PROBE_TPTP_7P5MM"))
    )
    (comp (ref "TP6")
      (value "PROBE_TPTP_7P5MM")
      (footprint "eagle-import:PROBE_TP_7P5MM")
      (libsource (lib "eagle-import") (part "PROBE_TPTP_7P5MM"))
    )
    (comp (ref "TP14")
      (value "PROBE_TPTP_5MM")
      (footprint "eagle-import:PROBE_TP_5MM")
      (libsource (lib "eagle-import") (part "PROBE_TPTP_5MM"))
    )
    (comp (ref "TP15")
      (value "PROBE_TPTP_5MM")
      (footprint "eagle-import:PROBE_TP_5MM")
      (libsource (lib "eagle-import") (part "PROBE_TPTP_5MM"))
    )
    (comp (ref "TP18")
      (value "PROBE_TPTP_5MM")
      (footprint "eagle-import:PROBE_TP_5MM")
      (libsource (lib "eagle-import") (part "PROBE_TPTP_5MM"))
    )
    (comp (ref "TP19")
      (value "PROBE_TPTP_5MM")
      (footprint "eagle-import:PROBE_TP_5MM")
      (libsource (lib "eagle-import") (part "PROBE_TPTP_5MM"))
    )
  )
  (nets
    (net (code "1") (name "+5V") (class "Default")
      (node (ref "C306") (pin "1") (pinfunction "1_1") (pintype "passive"))
      (node (ref "C407") (pin "1") (pinfunction "1_1") (pintype "passive"))
      (node (ref "C410") (pin "+") (pinfunction "+_+") (pintype "passive"))
      (node (ref "LED301") (pin "A") (pinfunction "A_A") (pintype "passive"))
      (node (ref "LED402") (pin "A") (pinfunction "A_A") (pintype "passive"))
      (node (ref "R301") (pin "3") (pinfunction "E_3") (pintype "passive"))
      (node (ref "R408") (pin "1") (pinfunction "1_1") (pintype "passive"))
      (node (ref "U301") (pin "5") (pinfunction "VCC_5") (pintype "power_in"))
      (node (ref "U402") (pin "3") (pinfunction "OUT_3") (pintype "passive"))
    )
    (net (code "2") (name "ABN1") (class "Default")
      (node (ref "R103") (pin "1") (pinfunction "1_1") (pintype "passive"))
      (node (ref "R105") (pin "1") (pinfunction "1_1") (pintype "passive"))
      (node (ref "R202") (pin "1") (pinfunction "1_1") (pintype "passive"))
      (node (ref "R204") (pin "1") (pinfunction "1_1") (pintype "passive"))
      (node (ref "T101") (pin "11") (pinfunction "F2_11") (pintype "passive"))
      (node (ref "TP18") (pin "TP") (pinfunction "1_TP") (pintype "passive"))
    )
    (net (code "3") (name "ABP1") (class "Default")
      (node (ref "R102") (pin "1") (pinfunction "1_1") (pintype "passive"))
      (node (ref "R104") (pin "1") (pinfunction "1_1") (pintype "passive"))
      (node (ref "R201") (pin "1") (pinfunction "1_1") (pintype "passive"))
      (node (ref "R203") (pin "1") (pinfunction "1_1") (pintype "passive"))
      (node (ref "T101") (pin "1") (pinfunction "S1_1") (pintype "passive"))
      (node (ref "TP19") (pin "TP") (pinfunction "1_TP") (pintype "passive"))
    )
    (net (code "4") (name "AN2") (class "Default")
      (node (ref "C107") (pin "2") (pinfunction "2_2") (pintype "passive"))
      (node (ref "R105") (pin "2") (pinfunction "2_2") (pintype "passive"))
      (node (ref "R107") (pin "1") (pinfunction "1_1") (pintype "passive"))
    )
    (net (code "5") (name "AN3") (class "Default")
      (node (ref "C107") (pin "1") (pinfunction "1_1") (pintype "passive"))
      (node (ref "L102") (pin "1") (pinfunction "1_1") (pintype "passive"))
      (node (ref "R111") (pin "2") (pinfunction "2_2") (pintype "passive"))
      (node (ref "R113") (pin "1") (pinfunction "1_1") (pintype "passive"))
      (node (ref "R115") (pin "1") (pinfunction "1_1") (pintype "passive"))
    )
    (net (code "6") (name "AN4") (class "Default")
      (node (ref "L102") (pin "2") (pinfunction "2_2") (pintype "passive"))
      (node (ref "Q102") (pin "G") (pinfunction "G_G") (pintype "passive"))
      (node (ref "R115") (pin "2") (pinfunction "2_2") (pintype "passive"))
      (node (ref "R117") (pin "1") (pinfunction "1_1") (pintype "passive"))
      (node (ref "R120") (pin "1") (pinfunction "1_1") (pintype "passive"))
      (node (ref "R121") (pin "1") (pinfunction "1_1") (pintype "passive"))
      (node (ref "TP3") (pin "TP") (pinfunction "1_TP") (pintype "passive"))
    )
    (net (code "7") (name "AN5") (class "Default")
      (node (ref "Q102") (pin "S") (pinfunction "S_S") (pintype "passive"))
      (node (ref "R123") (pin "1") (pinfunction "1_1") (pintype "passive"))
      (node (ref "R125") (pin "1") (pinfunction "1_1") (pintype "passive"))
      (node (ref "R127") (pin "1") (pinfunction "1_1") (pintype "passive"))
      (node (ref "R129") (pin "1") (pinfunction "1_1") (pintype "passive"))
      (node (ref "R131") (pin "1") (pinfunction "1_1") (pintype "passive"))
      (node (ref "TP6") (pin "TP") (pinfunction "1_TP") (pintype "passive"))
    )
    (net (code "8") (name "AN6") (class "Default")
      (node (ref "C115") (pin "1") (pinfunction "1_1") (pintype "passive"))
      (node (ref "R131") (pin "2") (pinfunction "2_2") (pintype "passive"))
      (node (ref "TP15") (pin "TP") (pinfunction "1_TP") (pintype "passive"))
    )
    (net (code "9") (name "AP2") (class "Default")
      (node (ref "C105") (pin "2") (pinfunction "2_2") (pintype "passive"))
      (node (ref "R104") (pin "2") (pinfunction "2_2") (pintype "passive"))
      (node (ref "R106") (pin "1") (pinfunction "1_1") (pintype "passive"))
    )
    (net (code "10") (name "AP3") (class "Default")
      (node (ref "C105") (pin "1") (pinfunction "1_1") (pintype "passive"))
      (node (ref "L101") (pin "1") (pinfunction "1_1") (pintype "passive"))
      (node (ref "R109") (pin "2") (pinfunction "2_2") (pintype "passive"))
      (node (ref "R112") (pin "1") (pinfunction "1_1") (pintype "passive"))
      (node (ref "R114") (pin "1") (pinfunction "1_1") (pintype "passive"))
    )
    (net (code "11") (name "AP4") (class "Default")
      (node (ref "L101") (pin "2") (pinfunction "2_2") (pintype "passive"))
      (node (ref "Q101") (pin "G") (pinfunction "G_G") (pintype "passive"))
      (node (ref "R114") (pin "2") (pinfunction "2_2") (pintype "passive"))
      (node (ref "R116") (pin "1") (pinfunction "1_1") (pintype "passive"))
      (node (ref "R118") (pin "1") (pinfunction "1_1") (pintype "passive"))
      (node (ref "R119") (pin "1") (pinfunction "1_1") (pintype "passive"))
      (node (ref "TP1") (pin "TP") (pinfunction "1_TP") (pintype "passive"))
    )
    (net (code "12") (name "AP5") (class "Default")
      (node (ref "Q101") (pin "S") (pinfunction "S_S") (pintype "passive"))
      (node (ref "R122") (pin "1") (pinfunction "1_1") (pintype "passive"))
      (node (ref "R124") (pin "1") (pinfunction "1_1") (pintype "passive"))
      (node (ref "R126") (pin "1") (pinfunction "1_1") (pintype "passive"))
      (node (ref "R128") (pin "1") (pinfunction "1_1") (pintype "passive"))
      (node (ref "R130") (pin "1") (pinfunction "1_1") (pintype "passive"))
      (node (ref "TP5") (pin "TP") (pinfunction "1_TP") (pintype "passive"))
    )
    (net (code "13") (name "AP6") (class "Default")
      (node (ref "C114") (pin "1") (pinfunction "1_1") (pintype "passive"))
      (node (ref "R130") (pin "2") (pinfunction "2_2") (pintype "passive"))
      (node (ref "TP14") (pin "TP") (pinfunction "1_TP") (pintype "passive"))
    )
    (net (code "14") (name "BN2") (class "Default")
      (node (ref "C204") (pin "2") (pinfunction "2_2") (pintype "passive"))
      (node (ref "R204") (pin "2") (pinfunction "2_2") (pintype "passive"))
      (node (ref "R206") (pin "1") (pinfunction "1_1") (pintype "passive"))
    )
    (net (code "15") (name "BN3") (class "Default")
      (node (ref "C204") (pin "1") (pinfunction "1_1") (pintype "passive"))
      (node (ref "L202") (pin "1") (pinfunction "1_1") (pintype "passive"))
      (node (ref "R210") (pin "2") (pinfunction "2_2") (pintype "passive"))
      (node (ref "R212") (pin "1") (pinfunction "1_1") (pintype "passive"))
      (node (ref "R214") (pin "1") (pinfunction "1_1") (pintype "passive"))
    )
    (net (code "16") (name "BN4") (class "Default")
      (node (ref "L202") (pin "2") (pinfunction "2_2") (pintype "passive"))
      (node (ref "Q202") (pin "G") (pinfunction "G_G") (pintype "passive"))
      (node (ref "R214") (pin "2") (pinfunction "2_2") (pintype "passive"))
      (node (ref "R216") (pin "1") (pinfunction "1_1") (pintype "passive"))
      (node (ref "R219") (pin "1") (pinfunction "1_1") (pintype "passive"))
      (node (ref "R220") (pin "1") (pinfunction "1_1") (pintype "passive"))
      (node (ref "TP9") (pin "TP") (pinfunction "1_TP") (pintype "passive"))
    )
    (net (code "17") (name "BN5") (class "Default")
      (node (ref "Q202") (pin "S") (pinfunction "S_S") (pintype "passive"))
      (node (ref "R222") (pin "1") (pinfunction "1_1") (pintype "passive"))
      (node (ref "R224") (pin "1") (pinfunction "1_1") (pintype "passive"))
      (node (ref "R226") (pin "1") (pinfunction "1_1") (pintype "passive"))
      (node (ref "R228") (pin "1") (pinfunction "1_1") (pintype "passive"))
      (node (ref "R230") (pin "1") (pinfunction "1_1") (pintype "passive"))
      (node (ref "TP10") (pin "TP") (pinfunction "1_TP") (pintype "passive"))
    )
    (net (code "18") (name "BN6") (class "Default")
      (node (ref "C212") (pin "1") (pinfunction "1_1") (pintype "passive"))
      (node (ref "R230") (pin "2") (pinfunction "2_2") (pintype "passive"))
      (node (ref "TP17") (pin "TP") (pinfunction "1_TP") (pintype "passive"))
    )
    (net (code "19") (name "BP2") (class "Default")
      (node (ref "C202") (pin "2") (pinfunction "2_2") (pintype "passive"))
      (node (ref "R203") (pin "2") (pinfunction "2_2") (pintype "passive"))
      (node (ref "R205") (pin "1") (pinfunction "1_1") (pintype "passive"))
    )
    (net (code "20") (name "BP3") (class "Default")
      (node (ref "C202") (pin "1") (pinfunction "1_1") (pintype "passive"))
      (node (ref "L201") (pin "1") (pinfunction "1_1") (pintype "passive"))
      (node (ref "R208") (pin "2") (pinfunction "2_2") (pintype "passive"))
      (node (ref "R211") (pin "1") (pinfunction "1_1") (pintype "passive"))
      (node (ref "R213") (pin "1") (pinfunction "1_1") (pintype "passive"))
    )
    (net (code "21") (name "BP4") (class "Default")
      (node (ref "L201") (pin "2") (pinfunction "2_2") (pintype "passive"))
      (node (ref "Q201") (pin "G") (pinfunction "G_G") (pintype "passive"))
      (node (ref "R213") (pin "2") (pinfunction "2_2") (pintype "passive"))
      (node (ref "R215") (pin "1") (pinfunction "1_1") (pintype "passive"))
      (node (ref "R217") (pin "1") (pinfunction "1_1") (pintype "passive"))
      (node (ref "R218") (pin "1") (pinfunction "1_1") (pintype "passive"))
      (node (ref "TP7") (pin "TP") (pinfunction "1_TP") (pintype "passive"))
    )
    (net (code "22") (name "BP5") (class "Default")
      (node (ref "Q201") (pin "S") (pinfunction "S_S") (pintype "passive"))
      (node (ref "R221") (pin "1") (pinfunction "1_1") (pintype "passive"))
      (node (ref "R223") (pin "1") (pinfunction "1_1") (pintype "passive"))
      (node (ref "R225") (pin "1") (pinfunction "1_1") (pintype "passive"))
      (node (ref "R227") (pin "1") (pinfunction "1_1") (pintype "passive"))
      (node (ref "R229") (pin "1") (pinfunction "1_1") (pintype "passive"))
      (node (ref "TP8") (pin "TP") (pinfunction "1_TP") (pintype "passive"))
    )
    (net (code "23") (name "BP6") (class "Default")
      (node (ref "C211") (pin "1") (pinfunction "1_1") (pintype "passive"))
      (node (ref "R229") (pin "2") (pinfunction "2_2") (pintype "passive"))
      (node (ref "TP16") (pin "TP") (pinfunction "1_TP") (pintype "passive"))
    )
    (net (code "24") (name "DRAINS_NEG") (class "Default")
      (node (ref "C113") (pin "2") (pinfunction "2_2") (pintype "passive"))
      (node (ref "C117") (pin "2") (pinfunction "2_2") (pintype "passive"))
      (node (ref "C210") (pin "2") (pinfunction "2_2") (pintype "passive"))
      (node (ref "L104") (pin "1") (pinfunction "1_1") (pintype "passive"))
      (node (ref "Q102") (pin "D") (pinfunction "D_D") (pintype "passive"))
      (node (ref "Q202") (pin "D") (pinfunction "D_D") (pintype "passive"))
      (node (ref "T102") (pin "8") (pinfunction "F5_8") (pintype "passive"))
      (node (ref "TP4") (pin "TP") (pinfunction "1_TP") (pintype "passive"))
    )
    (net (code "25") (name "DRAINS_POS") (class "Default")
      (node (ref "C112") (pin "2") (pinfunction "2_2") (pintype "passive"))
      (node (ref "C116") (pin "2") (pinfunction "2_2") (pintype "passive"))
      (node (ref "C209") (pin "2") (pinfunction "2_2") (pintype "passive"))
      (node (ref "L103") (pin "1") (pinfunction "1_1") (pintype "passive"))
      (node (ref "Q101") (pin "D") (pinfunction "D_D") (pintype "passive"))
      (node (ref "Q201") (pin "D") (pinfunction "D_D") (pintype "passive"))
      (node (ref "T102") (pin "6") (pinfunction "S6_6") (pintype "passive"))
      (node (ref "TP2") (pin "TP") (pinfunction "1_TP") (pintype "passive"))
    )
    (net (code "26") (name "GBIAS") (class "Default")
      (node (ref "Q302") (pin "2") (pinfunction "E_2") (pintype "passive"))
      (node (ref "Q303") (pin "2") (pinfunction "E_2") (pintype "passive"))
      (node (ref "R108") (pin "1") (pinfunction "1_1") (pintype "passive"))
      (node (ref "R110") (pin "1") (pinfunction "1_1") (pintype "passive"))
      (node (ref "R207") (pin "1") (pinfunction "1_1") (pintype "passive"))
      (node (ref "R209") (pin "1") (pinfunction "1_1") (pintype "passive"))
      (node (ref "R316") (pin "2") (pinfunction "2_2") (pintype "passive"))
      (node (ref "R317") (pin "2") (pinfunction "2_2") (pintype "passive"))
      (node (ref "TP11") (pin "TP") (pinfunction "1_TP") (pintype "passive"))
    )
    (net (code "27") (name "Net-(C104-Pad1)") (class "Default")
      (node (ref "C104") (pin "1") (pinfunction "1_1") (pintype "passive"))
      (node (ref "R108") (pin "2") (pinfunction "2_2") (pintype "passive"))
      (node (ref "R109") (pin "1") (pinfunction "1_1") (pintype "passive"))
    )
    (net (code "28") (name "Net-(C106-Pad1)") (class "Default")
      (node (ref "C106") (pin "1") (pinfunction "1_1") (pintype "passive"))
      (node (ref "R110") (pin "2") (pinfunction "2_2") (pintype "passive"))
      (node (ref "R111") (pin "1") (pinfunction "1_1") (pintype "passive"))
    )
    (net (code "29") (name "Net-(C108-Pad1)") (class "Default")
      (node (ref "C108") (pin "1") (pinfunction "1_1") (pintype "passive"))
      (node (ref "R112") (pin "2") (pinfunction "2_2") (pintype "passive"))
    )
    (net (code "30") (name "Net-(C109-Pad1)") (class "Default")
      (node (ref "C109") (pin "1") (pinfunction "1_1") (pintype "passive"))
      (node (ref "R113") (pin "2") (pinfunction "2_2") (pintype "passive"))
    )
    (net (code "31") (name "Net-(C110-Pad1)") (class "Default")
      (node (ref "C110") (pin "1") (pinfunction "1_1") (pintype "passive"))
      (node (ref "R116") (pin "2") (pinfunction "2_2") (pintype "passive"))
    )
    (net (code "32") (name "Net-(C111-Pad1)") (class "Default")
      (node (ref "C111") (pin "1") (pinfunction "1_1") (pintype "passive"))
      (node (ref "R117") (pin "2") (pinfunction "2_2") (pintype "passive"))
    )
    (net (code "33") (name "Net-(C112-Pad1)") (class "Default")
      (node (ref "C112") (pin "1") (pinfunction "1_1") (pintype "passive"))
      (node (ref "R118") (pin "2") (pinfunction "2_2") (pintype "passive"))
      (node (ref "R119") (pin "2") (pinfunction "2_2") (pintype "passive"))
    )
    (net (code "34") (name "Net-(C113-Pad1)") (class "Default")
      (node (ref "C113") (pin "1") (pinfunction "1_1") (pintype "passive"))
      (node (ref "R120") (pin "2") (pinfunction "2_2") (pintype "passive"))
      (node (ref "R121") (pin "2") (pinfunction "2_2") (pintype "passive"))
    )
    (net (code "35") (name "Net-(C201-Pad1)") (class "Default")
      (node (ref "C201") (pin "1") (pinfunction "1_1") (pintype "passive"))
      (node (ref "R207") (pin "2") (pinfunction "2_2") (pintype "passive"))
      (node (ref "R208") (pin "1") (pinfunction "1_1") (pintype "passive"))
    )
    (net (code "36") (name "Net-(C203-Pad1)") (class "Default")
      (node (ref "C203") (pin "1") (pinfunction "1_1") (pintype "passive"))
      (node (ref "R209") (pin "2") (pinfunction "2_2") (pintype "passive"))
      (node (ref "R210") (pin "1") (pinfunction "1_1") (pintype "passive"))
    )
    (net (code "37") (name "Net-(C205-Pad1)") (class "Default")
      (node (ref "C205") (pin "1") (pinfunction "1_1") (pintype "passive"))
      (node (ref "R211") (pin "2") (pinfunction "2_2") (pintype "passive"))
    )
    (net (code "38") (name "Net-(C206-Pad1)") (class "Default")
      (node (ref "C206") (pin "1") (pinfunction "1_1") (pintype "passive"))
      (node (ref "R212") (pin "2") (pinfunction "2_2") (pintype "passive"))
    )
    (net (code "39") (name "Net-(C207-Pad1)") (class "Default")
      (node (ref "C207") (pin "1") (pinfunction "1_1") (pintype "passive"))
      (node (ref "R215") (pin "2") (pinfunction "2_2") (pintype "passive"))
    )
    (net (code "40") (name "Net-(C208-Pad1)") (class "Default")
      (node (ref "C208") (pin "1") (pinfunction "1_1") (pintype "passive"))
      (node (ref "R216") (pin "2") (pinfunction "2_2") (pintype "passive"))
    )
    (net (code "41") (name "Net-(C209-Pad1)") (class "Default")
      (node (ref "C209") (pin "1") (pinfunction "1_1") (pintype "passive"))
      (node (ref "R217") (pin "2") (pinfunction "2_2") (pintype "passive"))
      (node (ref "R218") (pin "2") (pinfunction "2_2") (pintype "passive"))
    )
    (net (code "42") (name "Net-(C210-Pad1)") (class "Default")
      (node (ref "C210") (pin "1") (pinfunction "1_1") (pintype "passive"))
      (node (ref "R219") (pin "2") (pinfunction "2_2") (pintype "passive"))
      (node (ref "R220") (pin "2") (pinfunction "2_2") (pintype "passive"))
    )
    (net (code "43") (name "Net-(C302-Pad1)") (class "Default")
      (node (ref "C302") (pin "1") (pinfunction "1_1") (pintype "passive"))
      (node (ref "R313") (pin "1") (pinfunction "1_1") (pintype "passive"))
    )
    (net (code "44") (name "Net-(C304-Pad1)") (class "Default")
      (node (ref "C304") (pin "1") (pinfunction "1_1") (pintype "passive"))
      (node (ref "R314") (pin "2") (pinfunction "2_2") (pintype "passive"))
    )
    (net (code "45") (name "Net-(C405-Pad1)") (class "Default")
      (node (ref "C405") (pin "1") (pinfunction "1_1") (pintype "passive"))
      (node (ref "L401") (pin "2") (pinfunction "2_2") (pintype "passive"))
      (node (ref "L402") (pin "1") (pinfunction "1_1") (pintype "passive"))
      (node (ref "R404") (pin "1") (pinfunction "1_1") (pintype "passive"))
      (node (ref "R405") (pin "1") (pinfunction "1_1") (pintype "passive"))
    )
    (net (code "46") (name "Net-(D401-C1)") (class "Default")
      (node (ref "D401") (pin "K") (pinfunction "C1_K") (pintype "passive"))
      (node (ref "J401") (pin "2") (pinfunction "2_2") (pintype "passive"))
      (node (ref "R401") (pin "1") (pinfunction "1_1") (pintype "passive"))
    )
    (net (code "47") (name "Net-(D402-A1)") (class "Default")
      (node (ref "D402") (pin "A") (pinfunction "A1_A") (pintype "passive"))
      (node (ref "R402") (pin "1") (pinfunction "1_1") (pintype "passive"))
      (node (ref "R403") (pin "1") (pinfunction "1_1") (pintype "passive"))
    )
    (net (code "48") (name "Net-(D402-C1)") (class "Default")
      (node (ref "C401") (pin "+") (pinfunction "+_+") (pintype "passive"))
      (node (ref "C402") (pin "1") (pinfunction "1_1") (pintype "passive"))
      (node (ref "D402") (pin "C") (pinfunction "C1_C") (pintype "passive"))
      (node (ref "L401") (pin "1") (pinfunction "1_1") (pintype "passive"))
      (node (ref "R401") (pin "2") (pinfunction "2_2") (pintype "passive"))
    )
    (net (code "49") (name "Net-(J1-Pad1)") (class "Default")
      (node (ref "J1") (pin "1") (pinfunction "1_1") (pintype "passive"))
      (node (ref "J401") (pin "1") (pinfunction "1_1") (pintype "passive"))
    )
    (net (code "50") (name "Net-(J101-1)") (class "Default")
      (node (ref "C101") (pin "2") (pinfunction "2_2") (pintype "passive"))
      (node (ref "C102") (pin "2") (pinfunction "2_2") (pintype "passive"))
      (node (ref "C103") (pin "2") (pinfunction "2_2") (pintype "passive"))
      (node (ref "J101") (pin "C") (pinfunction "1_C") (pintype "passive"))
    )
    (net (code "51") (name "Net-(J102-1)") (class "Default")
      (node (ref "C118") (pin "2") (pinfunction "2_2") (pintype "passive"))
      (node (ref "C119") (pin "2") (pinfunction "2_2") (pintype "passive"))
      (node (ref "C120") (pin "2") (pinfunction "2_2") (pintype "passive"))
      (node (ref "J102") (pin "C") (pinfunction "1_C") (pintype "passive"))
    )
    (net (code "52") (name "Net-(J301-1)") (class "Default")
      (node (ref "J301") (pin "C") (pinfunction "1_C") (pintype "passive"))
      (node (ref "JP301") (pin "2") (pinfunction "2_2") (pintype "passive"))
      (node (ref "R302") (pin "1") (pinfunction "1_1") (pintype "passive"))
    )
    (net (code "53") (name "Net-(J301-GND1-PadG1)") (class "Default")
      (node (ref "J301") (pin "G1") (pinfunction "GND1_G1") (pintype "power_in"))
      (node (ref "J301") (pin "G2") (pinfunction "GND1_G2") (pintype "power_in"))
      (node (ref "J301") (pin "G3") (pinfunction "GND1_G3") (pintype "power_in"))
      (node (ref "J301") (pin "G4") (pinfunction "GND1_G4") (pintype "power_in"))
      (node (ref "JP301") (pin "1") (pinfunction "1_1") (pintype "passive"))
      (node (ref "R303") (pin "1") (pinfunction "1_1") (pintype "passive"))
    )
    (net (code "54") (name "Net-(J302-1)") (class "Default")
      (node (ref "J302") (pin "C") (pinfunction "1_C") (pintype "passive"))
      (node (ref "R304") (pin "1") (pinfunction "1_1") (pintype "passive"))
    )
    (net (code "55") (name "Net-(J402-Pad3)") (class "Default")
      (node (ref "J402") (pin "3") (pinfunction "3_3") (pintype "passive"))
      (node (ref "R408") (pin "2") (pinfunction "2_2") (pintype "passive"))
    )
    (net (code "56") (name "Net-(LED301-C)") (class "Default")
      (node (ref "LED301") (pin "K") (pinfunction "C_K") (pintype "passive"))
      (node (ref "R309") (pin "1") (pinfunction "1_1") (pintype "passive"))
    )
    (net (code "57") (name "Net-(LED401-C)") (class "Default")
      (node (ref "LED401") (pin "K") (pinfunction "C_K") (pintype "passive"))
      (node (ref "R406") (pin "1") (pinfunction "1_1") (pintype "passive"))
    )
    (net (code "58") (name "Net-(LED402-C)") (class "Default")
      (node (ref "LED402") (pin "K") (pinfunction "C_K") (pintype "passive"))
      (node (ref "R407") (pin "1") (pinfunction "1_1") (pintype "passive"))
    )
    (net (code "59") (name "Net-(Q301-D)") (class "Default")
      (node (ref "Q301") (pin "3") (pinfunction "D_3") (pintype "passive"))
      (node (ref "R308") (pin "2") (pinfunction "2_2") (pintype "passive"))
      (node (ref "U302") (pin "5") (pinfunction "+IN_5") (pintype "input"))
    )
    (net (code "60") (name "Net-(Q301-G)") (class "Default")
      (node (ref "Q301") (pin "1") (pinfunction "G_1") (pintype "passive"))
      (node (ref "R309") (pin "2") (pinfunction "2_2") (pintype "passive"))
      (node (ref "U301") (pin "4") (pinfunction "O_4") (pintype "output"))
    )
    (net (code "61") (name "Net-(Q302-B)") (class "Default")
      (node (ref "Q302") (pin "1") (pinfunction "B_1") (pintype "passive"))
      (node (ref "Q303") (pin "1") (pinfunction "B_1") (pintype "passive"))
      (node (ref "R315") (pin "2") (pinfunction "2_2") (pintype "passive"))
      (node (ref "R316") (pin "1") (pinfunction "1_1") (pintype "passive"))
    )
    (net (code "62") (name "Net-(R301-S)") (class "Default")
      (node (ref "C301") (pin "1") (pinfunction "1_1") (pintype "passive"))
      (node (ref "R301") (pin "2") (pinfunction "S_2") (pintype "passive"))
      (node (ref "U302") (pin "12") (pinfunction "+IN_12") (pintype "input"))
    )
    (net (code "63") (name "Net-(T101-F1)") (class "Default")
      (node (ref "R101") (pin "1") (pinfunction "1_1") (pintype "passive"))
      (node (ref "T101") (pin "12") (pinfunction "F1_12") (pintype "passive"))
      (node (ref "T101") (pin "2") (pinfunction "S2_2") (pintype "passive"))
    )
    (net (code "64") (name "Net-(T101-F4)") (class "Default")
      (node (ref "T101") (pin "3") (pinfunction "S3_3") (pintype "passive"))
      (node (ref "T101") (pin "9") (pinfunction "F4_9") (pintype "passive"))
    )
    (net (code "65") (name "Net-(T101-F5)") (class "Default")
      (node (ref "C101") (pin "1") (pinfunction "1_1") (pintype "passive"))
      (node (ref "T101") (pin "4") (pinfunction "S4_4") (pintype "passive"))
      (node (ref "T101") (pin "8") (pinfunction "F5_8") (pintype "passive"))
    )
    (net (code "66") (name "Net-(T101-F6)") (class "Default")
      (node (ref "C102") (pin "1") (pinfunction "1_1") (pintype "passive"))
      (node (ref "T101") (pin "5") (pinfunction "S5_5") (pintype "passive"))
      (node (ref "T101") (pin "7") (pinfunction "F6_7") (pintype "passive"))
    )
    (net (code "67") (name "Net-(T101-S6)") (class "Default")
      (node (ref "C103") (pin "1") (pinfunction "1_1") (pintype "passive"))
      (node (ref "T101") (pin "6") (pinfunction "S6_6") (pintype "passive"))
    )
    (net (code "68") (name "Net-(T102-F1)") (class "Default")
      (node (ref "C119") (pin "1") (pinfunction "1_1") (pintype "passive"))
      (node (ref "T102") (pin "12") (pinfunction "F1_12") (pintype "passive"))
      (node (ref "T102") (pin "2") (pinfunction "S2_2") (pintype "passive"))
    )
    (net (code "69") (name "Net-(T102-F2)") (class "Default")
      (node (ref "C118") (pin "1") (pinfunction "1_1") (pintype "passive"))
      (node (ref "T102") (pin "11") (pinfunction "F2_11") (pintype "passive"))
      (node (ref "T102") (pin "3") (pinfunction "S3_3") (pintype "passive"))
    )
    (net (code "70") (name "Net-(T102-F3)") (class "Default")
      (node (ref "T102") (pin "10") (pinfunction "F3_10") (pintype "passive"))
      (node (ref "T102") (pin "4") (pinfunction "S4_4") (pintype "passive"))
    )
    (net (code "71") (name "Net-(T102-F6)") (class "Default")
      (node (ref "R132") (pin "2") (pinfunction "2_2") (pintype "passive"))
      (node (ref "T102") (pin "5") (pinfunction "S5_5") (pintype "passive"))
      (node (ref "T102") (pin "7") (pinfunction "F6_7") (pintype "passive"))
    )
    (net (code "72") (name "Net-(T102-S1)") (class "Default")
      (node (ref "C120") (pin "1") (pinfunction "1_1") (pintype "passive"))
      (node (ref "T102") (pin "1") (pinfunction "S1_1") (pintype "passive"))
    )
    (net (code "73") (name "Net-(TP12-1)") (class "Default")
      (node (ref "R310") (pin "1") (pinfunction "1_1") (pintype "passive"))
      (node (ref "TP12") (pin "TP") (pinfunction "1_TP") (pintype "passive"))
      (node (ref "U302") (pin "6") (pinfunction "-IN_6") (pintype "input"))
      (node (ref "U302") (pin "7") (pinfunction "OUT_7") (pintype "output"))
    )
    (net (code "74") (name "Net-(TP13-1)") (class "Default")
      (node (ref "R306") (pin "2") (pinfunction "2_2") (pintype "passive"))
      (node (ref "TP13") (pin "TP") (pinfunction "1_TP") (pintype "passive"))
      (node (ref "U302") (pin "13") (pinfunction "-IN_13") (pintype "input"))
      (node (ref "U302") (pin "14") (pinfunction "OUT_14") (pintype "output"))
    )
    (net (code "75") (name "Net-(U301A-I)") (class "Default")
      (node (ref "R304") (pin "2") (pinfunction "2_2") (pintype "passive"))
      (node (ref "R307") (pin "1") (pinfunction "1_1") (pintype "passive"))
      (node (ref "U301") (pin "2") (pinfunction "I_2") (pintype "input"))
    )
    (net (code "76") (name "Net-(U302A-+IN)") (class "Default")
      (node (ref "C303") (pin "1") (pinfunction "1_1") (pintype "passive"))
      (node (ref "R310") (pin "2") (pinfunction "2_2") (pintype "passive"))
      (node (ref "R311") (pin "1") (pinfunction "1_1") (pintype "passive"))
      (node (ref "U302") (pin "3") (pinfunction "+IN_3") (pintype "input"))
    )
    (net (code "77") (name "Net-(U302A--IN)") (class "Default")
      (node (ref "C304") (pin "2") (pinfunction "2_2") (pintype "passive"))
      (node (ref "R312") (pin "2") (pinfunction "2_2") (pintype "passive"))
      (node (ref "R313") (pin "2") (pinfunction "2_2") (pintype "passive"))
      (node (ref "R317") (pin "1") (pinfunction "1_1") (pintype "passive"))
      (node (ref "U302") (pin "2") (pinfunction "-IN_2") (pintype "input"))
    )
    (net (code "78") (name "Net-(U302A-OUT)") (class "Default")
      (node (ref "R314") (pin "1") (pinfunction "1_1") (pintype "passive"))
      (node (ref "R315") (pin "1") (pinfunction "1_1") (pintype "passive"))
      (node (ref "U302") (pin "1") (pinfunction "OUT_1") (pintype "output"))
    )
    (net (code "79") (name "Net-(U302C-+IN)") (class "Default")
      (node (ref "R303") (pin "2") (pinfunction "2_2") (pintype "passive"))
      (node (ref "R306") (pin "1") (pinfunction "1_1") (pintype "passive"))
      (node (ref "U302") (pin "10") (pinfunction "+IN_10") (pintype "input"))
    )
    (net (code "80") (name "Net-(U302C--IN)") (class "Default")
      (node (ref "JP302") (pin "1") (pinfunction "1_1") (pintype "passive"))
      (node (ref "R302") (pin "2") (pinfunction "2_2") (pintype "passive"))
      (node (ref "R305") (pin "1") (pinfunction "1_1") (pintype "passive"))
      (node (ref "U302") (pin "9") (pinfunction "-IN_9") (pintype "input"))
    )
    (net (code "81") (name "Net-(U302C-OUT)") (class "Default")
      (node (ref "JP302") (pin "2") (pinfunction "2_2") (pintype "passive"))
      (node (ref "R305") (pin "2") (pinfunction "2_2") (pintype "passive"))
      (node (ref "R308") (pin "1") (pinfunction "1_1") (pintype "passive"))
      (node (ref "U302") (pin "8") (pinfunction "OUT_8") (pintype "output"))
    )
    (net (code "82") (name "Net-(U401-IN)") (class "Default")
      (node (ref "C403") (pin "1") (pinfunction "1_1") (pintype "passive"))
      (node (ref "R402") (pin "2") (pinfunction "2_2") (pintype "passive"))
      (node (ref "U401") (pin "1") (pinfunction "IN_1") (pintype "input"))
    )
    (net (code "83") (name "Net-(U402-IN)") (class "Default")
      (node (ref "C404") (pin "1") (pinfunction "1_1") (pintype "passive"))
      (node (ref "R403") (pin "2") (pinfunction "2_2") (pintype "passive"))
      (node (ref "U402") (pin "1") (pinfunction "IN_1") (pintype "input"))
    )
    (net (code "84") (name "V+") (class "Default")
      (node (ref "C305") (pin "1") (pinfunction "1_1") (pintype "passive"))
      (node (ref "C406") (pin "1") (pinfunction "1_1") (pintype "passive"))
      (node (ref "C409") (pin "+") (pinfunction "+_+") (pintype "passive"))
      (node (ref "J402") (pin "2") (pinfunction "2_2") (pintype "passive"))
      (node (ref "LED401") (pin "A") (pinfunction "A_A") (pintype "passive"))
      (node (ref "Q303") (pin "3") (pinfunction "C_3") (pintype "passive"))
      (node (ref "U302") (pin "4") (pinfunction "V+_4") (pintype "power_in"))
      (node (ref "U401") (pin "3") (pinfunction "OUT_3") (pintype "passive"))
    )
    (net (code "85") (name "V-") (class "Default")
      (node (ref "C104") (pin "2") (pinfunction "2_2") (pintype "passive"))
      (node (ref "C106") (pin "2") (pinfunction "2_2") (pintype "passive"))
      (node (ref "C108") (pin "2") (pinfunction "2_2") (pintype "passive"))
      (node (ref "C109") (pin "2") (pinfunction "2_2") (pintype "passive"))
      (node (ref "C110") (pin "2") (pinfunction "2_2") (pintype "passive"))
      (node (ref "C111") (pin "2") (pinfunction "2_2") (pintype "passive"))
      (node (ref "C114") (pin "2") (pinfunction "2_2") (pintype "passive"))
      (node (ref "C115") (pin "2") (pinfunction "2_2") (pintype "passive"))
      (node (ref "C201") (pin "2") (pinfunction "2_2") (pintype "passive"))
      (node (ref "C203") (pin "2") (pinfunction "2_2") (pintype "passive"))
      (node (ref "C205") (pin "2") (pinfunction "2_2") (pintype "passive"))
      (node (ref "C206") (pin "2") (pinfunction "2_2") (pintype "passive"))
      (node (ref "C207") (pin "2") (pinfunction "2_2") (pintype "passive"))
      (node (ref "C208") (pin "2") (pinfunction "2_2") (pintype "passive"))
      (node (ref "C211") (pin "2") (pinfunction "2_2") (pintype "passive"))
      (node (ref "C212") (pin "2") (pinfunction "2_2") (pintype "passive"))
      (node (ref "C301") (pin "2") (pinfunction "2_2") (pintype "passive"))
      (node (ref "C302") (pin "2") (pinfunction "2_2") (pintype "passive"))
      (node (ref "C303") (pin "2") (pinfunction "2_2") (pintype "passive"))
      (node (ref "C305") (pin "2") (pinfunction "2_2") (pintype "passive"))
      (node (ref "C306") (pin "2") (pinfunction "2_2") (pintype "passive"))
      (node (ref "C401") (pin "-") (pinfunction "-_-") (pintype "passive"))
      (node (ref "C402") (pin "2") (pinfunction "2_2") (pintype "passive"))
      (node (ref "C403") (pin "2") (pinfunction "2_2") (pintype "passive"))
      (node (ref "C404") (pin "2") (pinfunction "2_2") (pintype "passive"))
      (node (ref "C405") (pin "2") (pinfunction "2_2") (pintype "passive"))
      (node (ref "C406") (pin "2") (pinfunction "2_2") (pintype "passive"))
      (node (ref "C407") (pin "2") (pinfunction "2_2") (pintype "passive"))
      (node (ref "C408") (pin "2") (pinfunction "2_2") (pintype "passive"))
      (node (ref "C409") (pin "-") (pinfunction "-_-") (pintype "passive"))
      (node (ref "C410") (pin "-") (pinfunction "-_-") (pintype "passive"))
      (node (ref "C411") (pin "2") (pinfunction "2_2") (pintype "passive"))
      (node (ref "C412") (pin "2") (pinfunction "2_2") (pintype "passive"))
      (node (ref "C413") (pin "2") (pinfunction "2_2") (pintype "passive"))
      (node (ref "D401") (pin "A") (pinfunction "A1_A") (pintype "passive"))
      (node (ref "H401") (pin "B3,2") (pinfunction "MOUNT_B3,2") (pintype "passive"))
      (node (ref "H402") (pin "B3,2") (pinfunction "MOUNT_B3,2") (pintype "passive"))
      (node (ref "H403") (pin "B3,2") (pinfunction "MOUNT_B3,2") (pintype "passive"))
      (node (ref "H404") (pin "B3,2") (pinfunction "MOUNT_B3,2") (pintype "passive"))
      (node (ref "J1") (pin "2") (pinfunction "2_2") (pintype "passive"))
      (node (ref "J101") (pin "G1") (pinfunction "GND1_G1") (pintype "power_in"))
      (node (ref "J101") (pin "G2") (pinfunction "GND1_G2") (pintype "power_in"))
      (node (ref "J101") (pin "G3") (pinfunction "GND1_G3") (pintype "power_in"))
      (node (ref "J101") (pin "G4") (pinfunction "GND1_G4") (pintype "power_in"))
      (node (ref "J102") (pin "G1") (pinfunction "GND1_G1") (pintype "power_in"))
      (node (ref "J102") (pin "G2") (pinfunction "GND1_G2") (pintype "power_in"))
      (node (ref "J102") (pin "G3") (pinfunction "GND1_G3") (pintype "power_in"))
      (node (ref "J102") (pin "G4") (pinfunction "GND1_G4") (pintype "power_in"))
      (node (ref "J302") (pin "G1") (pinfunction "GND1_G1") (pintype "power_in"))
      (node (ref "J302") (pin "G2") (pinfunction "GND1_G2") (pintype "power_in"))
      (node (ref "J302") (pin "G3") (pinfunction "GND1_G3") (pintype "power_in"))
      (node (ref "J302") (pin "G4") (pinfunction "GND1_G4") (pintype "power_in"))
      (node (ref "J402") (pin "1") (pinfunction "1_1") (pintype "passive"))
      (node (ref "Q301") (pin "2") (pinfunction "S_2") (pintype "passive"))
      (node (ref "Q302") (pin "3") (pinfunction "C_3") (pintype "passive"))
      (node (ref "R101") (pin "2") (pinfunction "2_2") (pintype "passive"))
      (node (ref "R102") (pin "2") (pinfunction "2_2") (pintype "passive"))
      (node (ref "R103") (pin "2") (pinfunction "2_2") (pintype "passive"))
      (node (ref "R106") (pin "2") (pinfunction "2_2") (pintype "passive"))
      (node (ref "R107") (pin "2") (pinfunction "2_2") (pintype "passive"))
      (node (ref "R122") (pin "2") (pinfunction "2_2") (pintype "passive"))
      (node (ref "R123") (pin "2") (pinfunction "2_2") (pintype "passive"))
      (node (ref "R124") (pin "2") (pinfunction "2_2") (pintype "passive"))
      (node (ref "R125") (pin "2") (pinfunction "2_2") (pintype "passive"))
      (node (ref "R126") (pin "2") (pinfunction "2_2") (pintype "passive"))
      (node (ref "R127") (pin "2") (pinfunction "2_2") (pintype "passive"))
      (node (ref "R128") (pin "2") (pinfunction "2_2") (pintype "passive"))
      (node (ref "R129") (pin "2") (pinfunction "2_2") (pintype "passive"))
      (node (ref "R201") (pin "2") (pinfunction "2_2") (pintype "passive"))
      (node (ref "R202") (pin "2") (pinfunction "2_2") (pintype "passive"))
      (node (ref "R205") (pin "2") (pinfunction "2_2") (pintype "passive"))
      (node (ref "R206") (pin "2") (pinfunction "2_2") (pintype "passive"))
      (node (ref "R221") (pin "2") (pinfunction "2_2") (pintype "passive"))
      (node (ref "R222") (pin "2") (pinfunction "2_2") (pintype "passive"))
      (node (ref "R223") (pin "2") (pinfunction "2_2") (pintype "passive"))
      (node (ref "R224") (pin "2") (pinfunction "2_2") (pintype "passive"))
      (node (ref "R225") (pin "2") (pinfunction "2_2") (pintype "passive"))
      (node (ref "R226") (pin "2") (pinfunction "2_2") (pintype "passive"))
      (node (ref "R227") (pin "2") (pinfunction "2_2") (pintype "passive"))
      (node (ref "R228") (pin "2") (pinfunction "2_2") (pintype "passive"))
      (node (ref "R301") (pin "1") (pinfunction "A_1") (pintype "passive"))
      (node (ref "R307") (pin "2") (pinfunction "2_2") (pintype "passive"))
      (node (ref "R311") (pin "2") (pinfunction "2_2") (pintype "passive"))
      (node (ref "R312") (pin "1") (pinfunction "1_1") (pintype "passive"))
      (node (ref "R406") (pin "2") (pinfunction "2_2") (pintype "passive"))
      (node (ref "R407") (pin "2") (pinfunction "2_2") (pintype "passive"))
      (node (ref "T101") (pin "10") (pinfunction "F3_10") (pintype "passive"))
      (node (ref "T102") (pin "9") (pinfunction "F4_9") (pintype "passive"))
      (node (ref "TP1") (pin "GND") (pinfunction "GND1_GND") (pintype "power_in"))
      (node (ref "TP10") (pin "GND") (pinfunction "GND1_GND") (pintype "power_in"))
      (node (ref "TP11") (pin "GND") (pinfunction "GND1_GND") (pintype "power_in"))
      (node (ref "TP12") (pin "GND") (pinfunction "GND1_GND") (pintype "power_in"))
      (node (ref "TP13") (pin "GND") (pinfunction "GND1_GND") (pintype "power_in"))
      (node (ref "TP14") (pin "GND") (pinfunction "GND1_GND") (pintype "power_in"))
      (node (ref "TP15") (pin "GND") (pinfunction "GND1_GND") (pintype "power_in"))
      (node (ref "TP16") (pin "GND") (pinfunction "GND1_GND") (pintype "power_in"))
      (node (ref "TP17") (pin "GND") (pinfunction "GND1_GND") (pintype "power_in"))
      (node (ref "TP18") (pin "GND") (pinfunction "GND1_GND") (pintype "power_in"))
      (node (ref "TP19") (pin "GND") (pinfunction "GND1_GND") (pintype "power_in"))
      (node (ref "TP2") (pin "GND") (pinfunction "GND1_GND") (pintype "power_in"))
      (node (ref "TP3") (pin "GND") (pinfunction "GND1_GND") (pintype "power_in"))
      (node (ref "TP4") (pin "GND") (pinfunction "GND1_GND") (pintype "power_in"))
      (node (ref "TP5") (pin "GND") (pinfunction "GND1_GND") (pintype "power_in"))
      (node (ref "TP6") (pin "GND") (pinfunction "GND1_GND") (pintype "power_in"))
      (node (ref "TP7") (pin "GND") (pinfunction "GND1_GND") (pintype "power_in"))
      (node (ref "TP8") (pin "GND") (pinfunction "GND1_GND") (pintype "power_in"))
      (node (ref "TP9") (pin "GND") (pinfunction "GND1_GND") (pintype "power_in"))
      (node (ref "U301") (pin "3") (pinfunction "GND_3") (pintype "power_in"))
      (node (ref "U302") (pin "11") (pinfunction "V-_11") (pintype "power_in"))
      (node (ref "U401") (pin "2") (pinfunction "GND_2") (pintype "input"))
      (node (ref "U402") (pin "2") (pinfunction "GND_2") (pintype "input"))
      (node (ref "X402") (pin "P1") (pinfunction "P$1_P1") (pintype "bidirectional"))
      (node (ref "X402") (pin "P2") (pinfunction "P$2_P2") (pintype "bidirectional"))
    )
    (net (code "86") (name "VB") (class "Default")
      (node (ref "C116") (pin "1") (pinfunction "1_1") (pintype "passive"))
      (node (ref "C117") (pin "1") (pinfunction "1_1") (pintype "passive"))
      (node (ref "C408") (pin "1") (pinfunction "1_1") (pintype "passive"))
      (node (ref "C411") (pin "1") (pinfunction "1_1") (pintype "passive"))
      (node (ref "C412") (pin "1") (pinfunction "1_1") (pintype "passive"))
      (node (ref "C413") (pin "1") (pinfunction "1_1") (pintype "passive"))
      (node (ref "L103") (pin "2") (pinfunction "2_2") (pintype "passive"))
      (node (ref "L104") (pin "2") (pinfunction "2_2") (pintype "passive"))
      (node (ref "L402") (pin "2") (pinfunction "2_2") (pintype "passive"))
      (node (ref "R132") (pin "1") (pinfunction "1_1") (pintype "passive"))
      (node (ref "R404") (pin "2") (pinfunction "2_2") (pintype "passive"))
      (node (ref "R405") (pin "2") (pinfunction "2_2") (pintype "passive"))
    )
    (net (code "87") (name "unconnected-(J402-Pad4)") (class "Default")
      (node (ref "J402") (pin "4") (pinfunction "4_4") (pintype "passive"))
    )
  )
)
